# Fathom-S.net
KiCad netlist of a schematic drawn in EAGLE
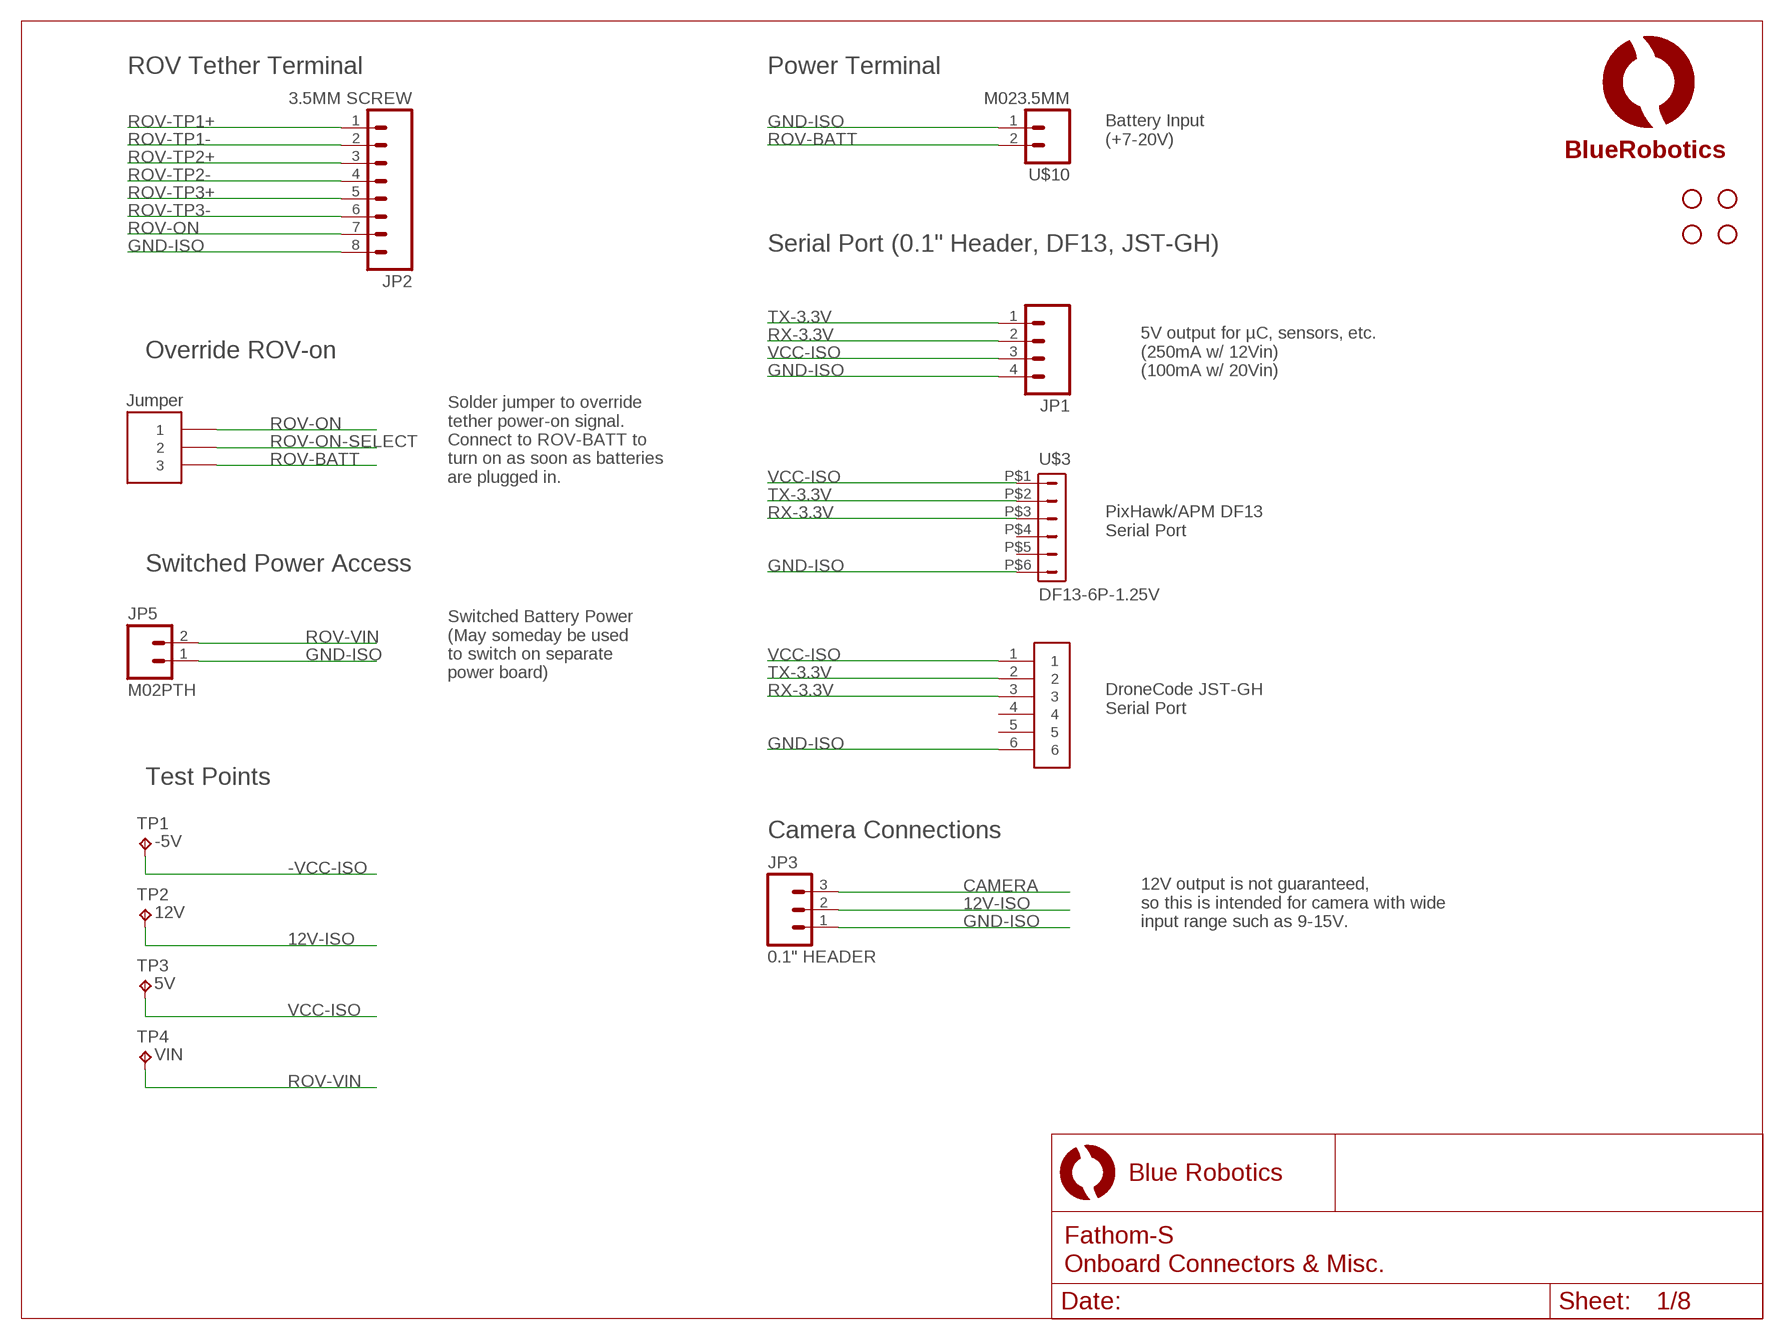
[diagram p0: schematic, sheet 1]
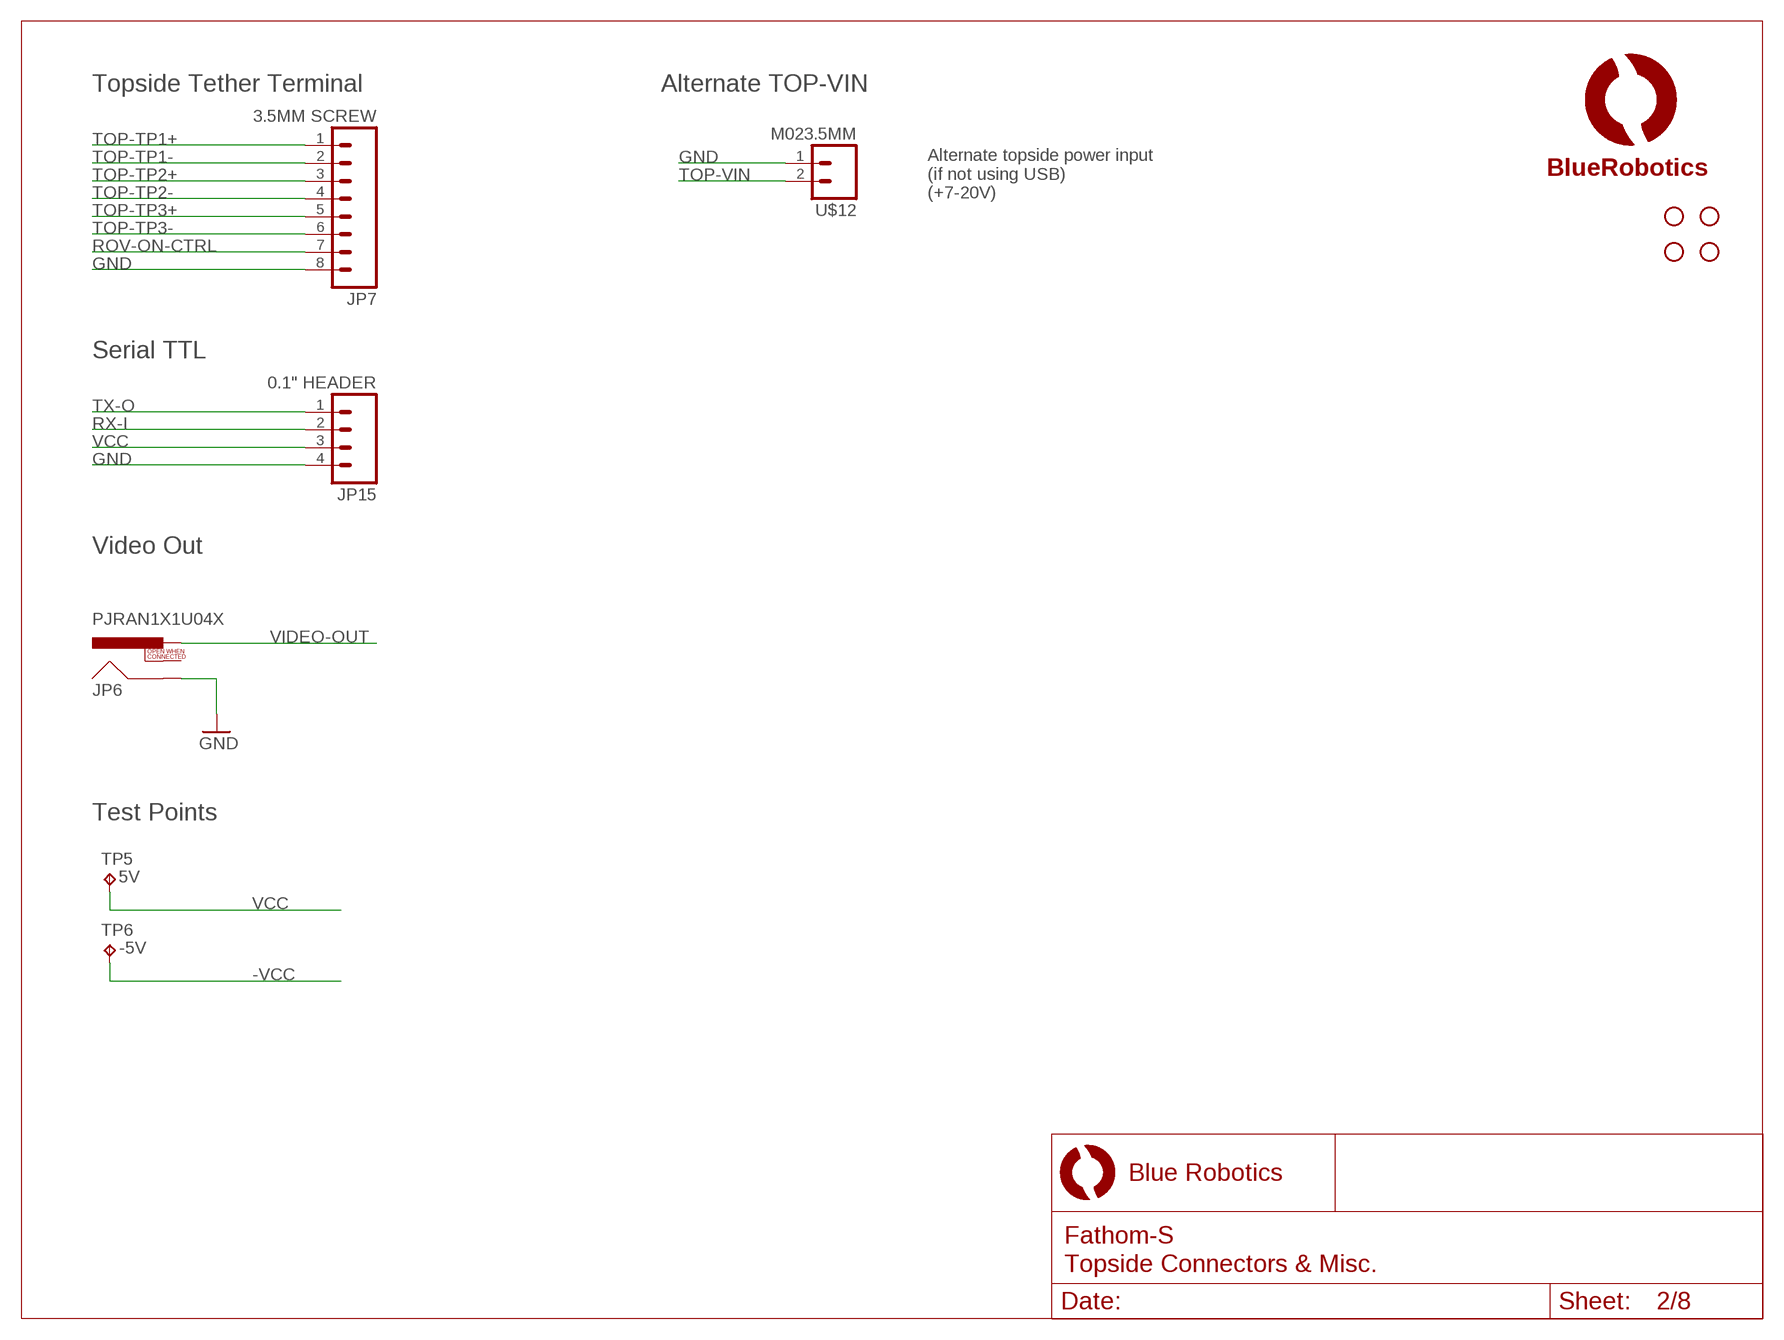
[diagram p1: schematic, sheet 2]
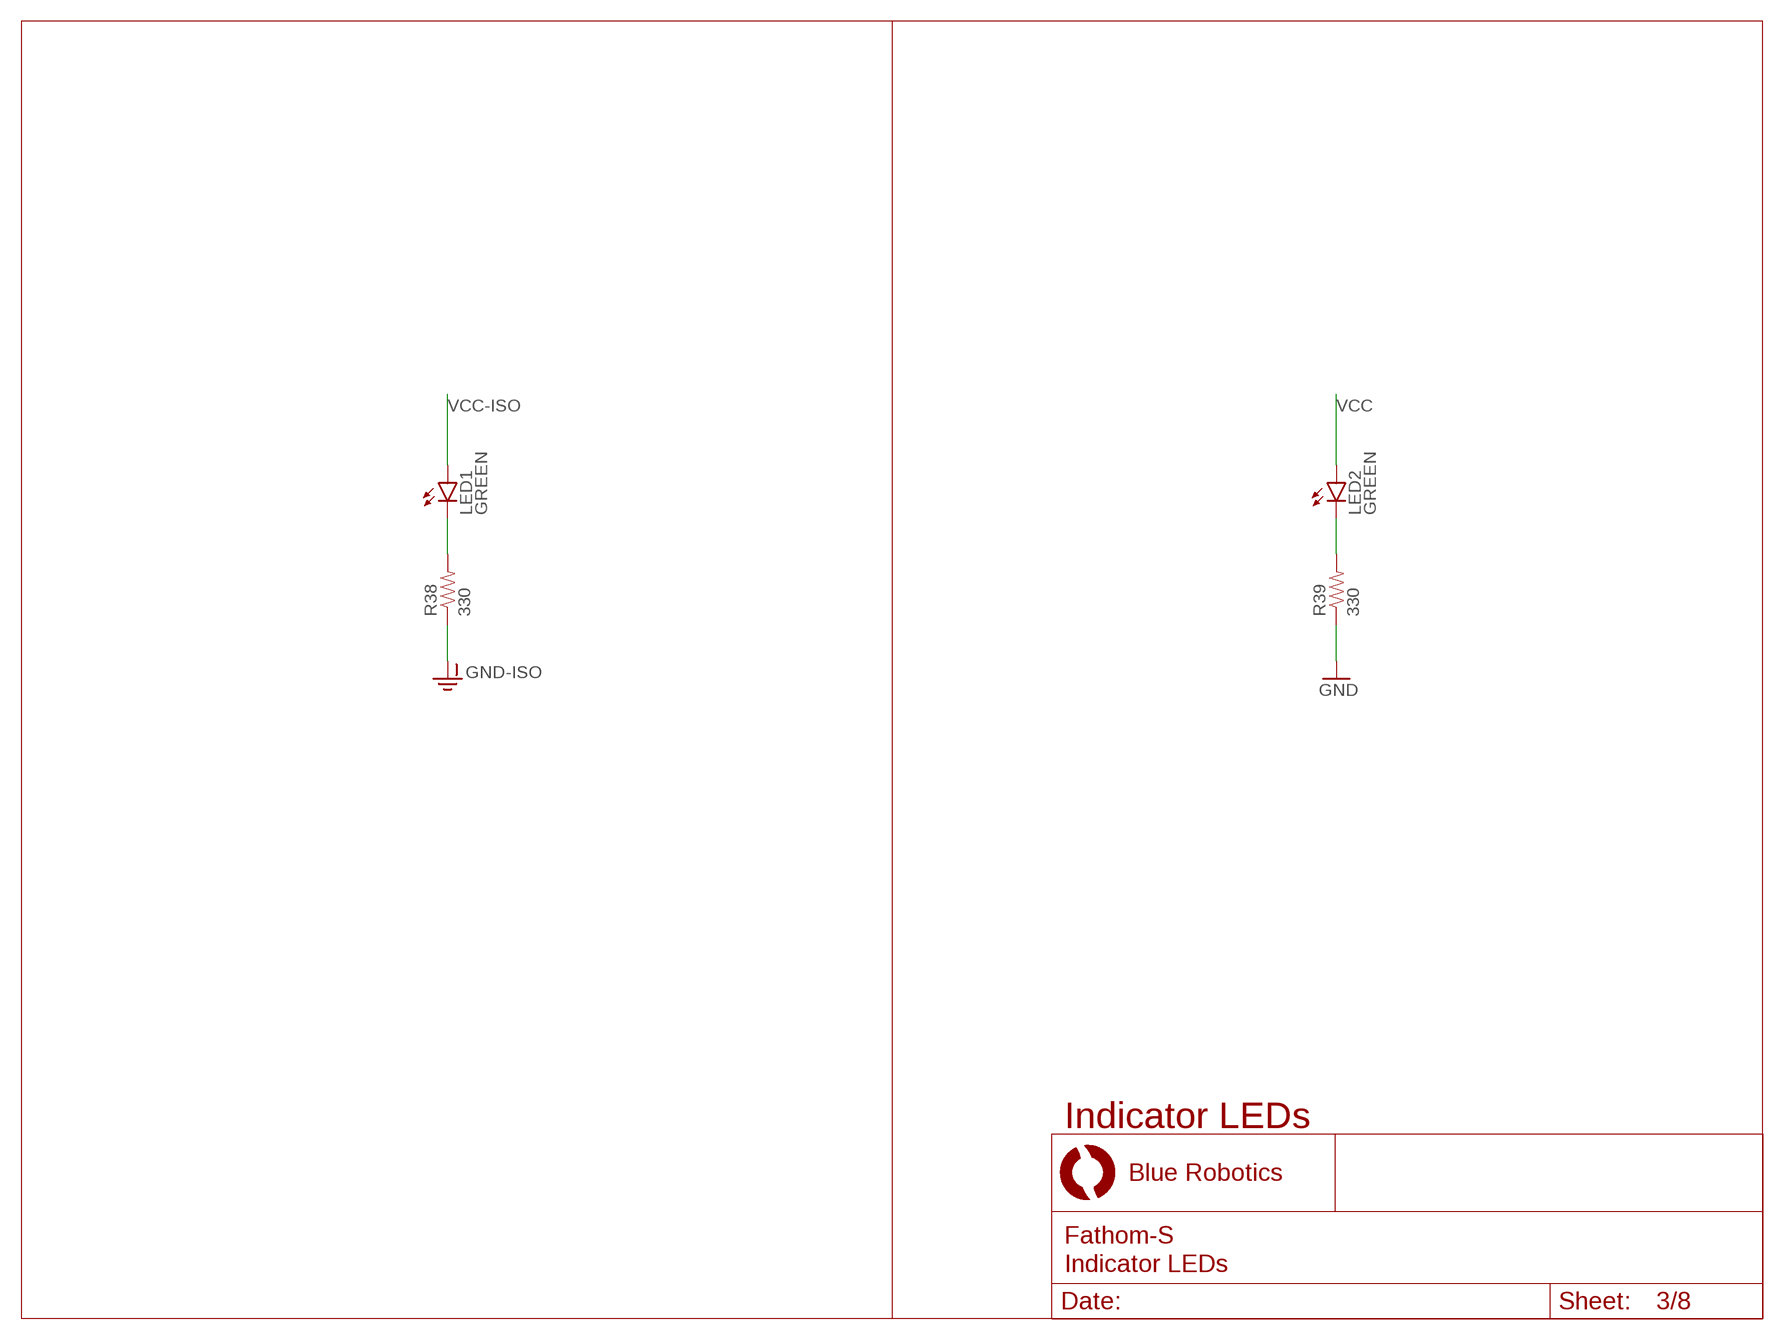
[diagram p2: schematic, sheet 3]
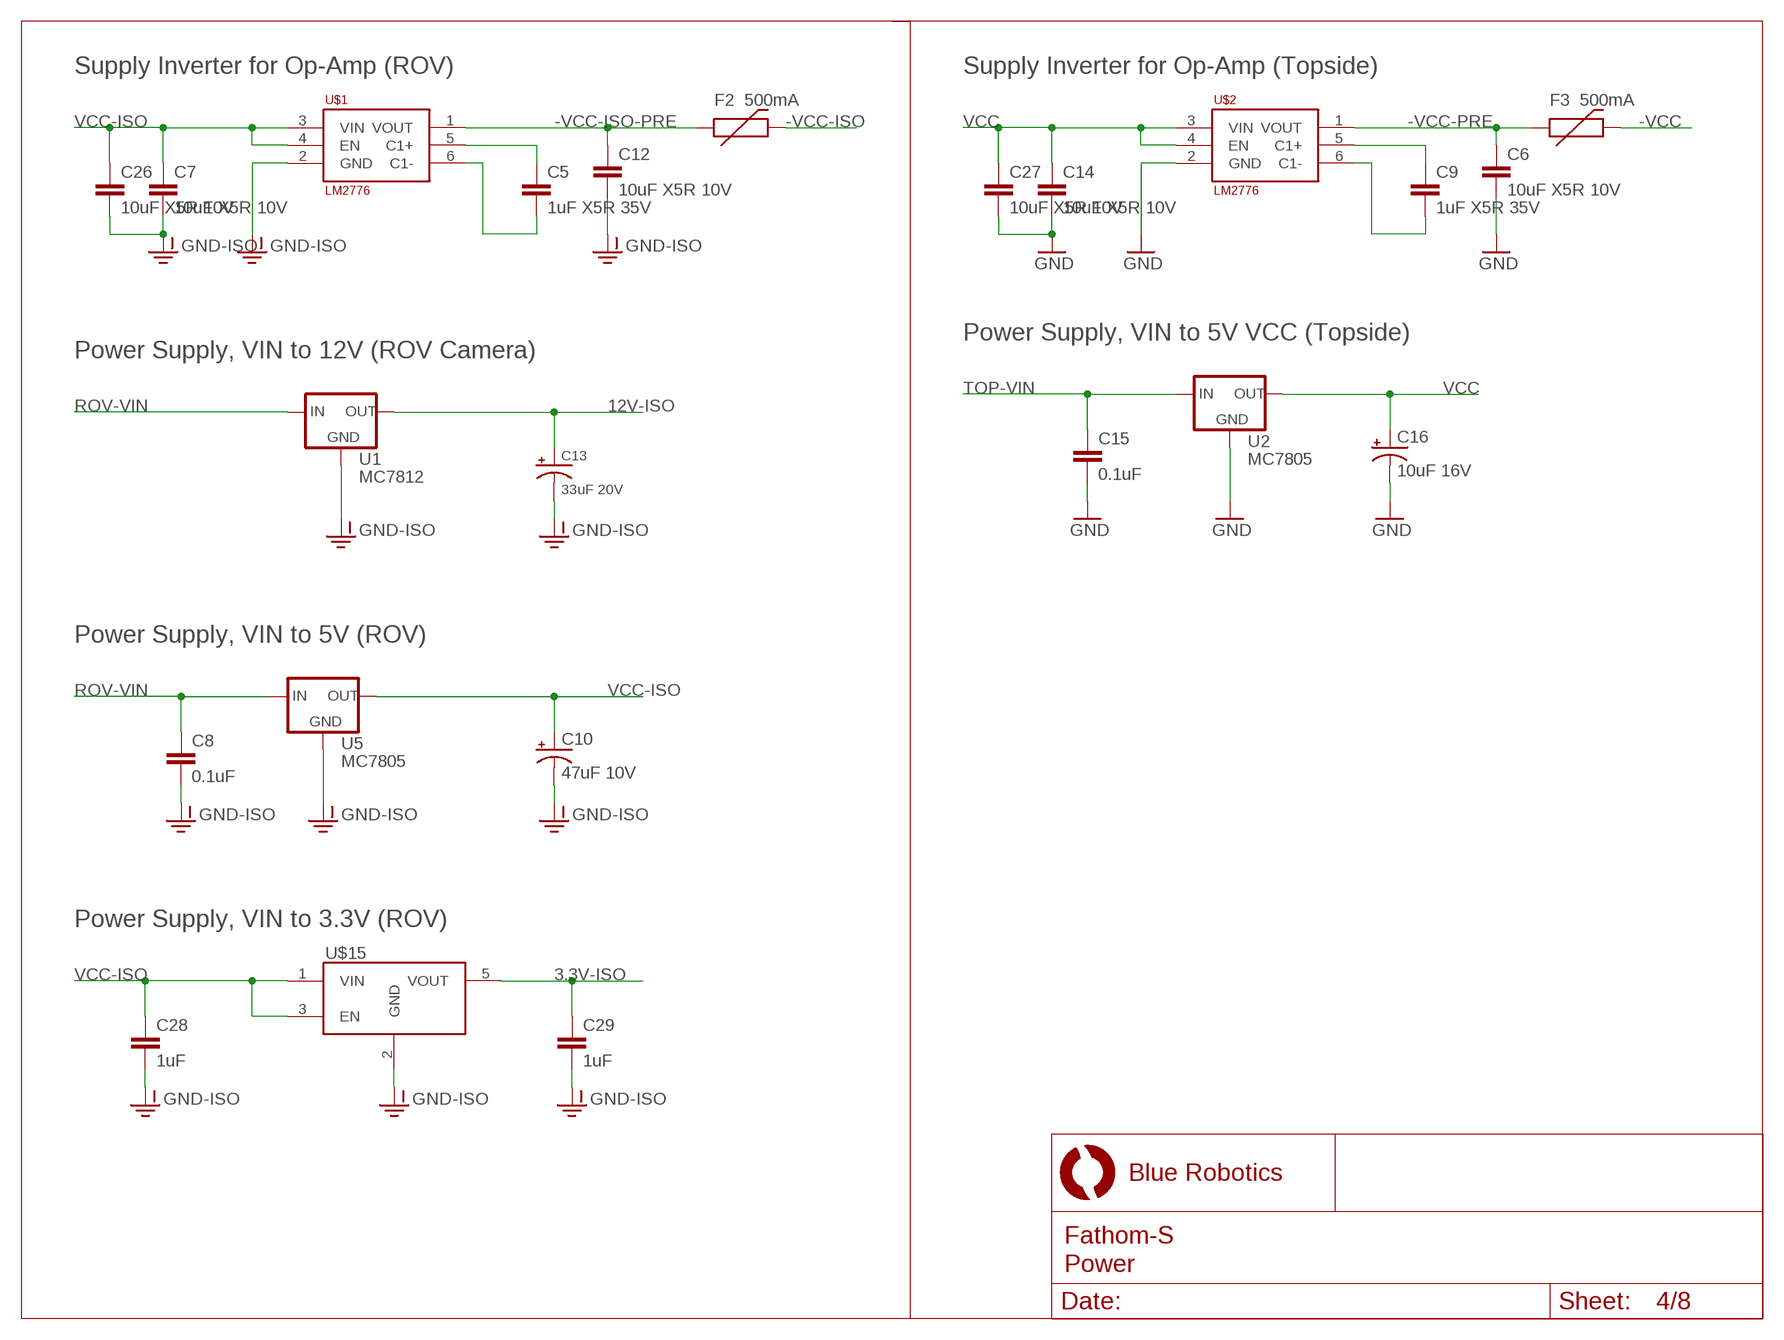
[diagram p3: schematic, sheet 4]
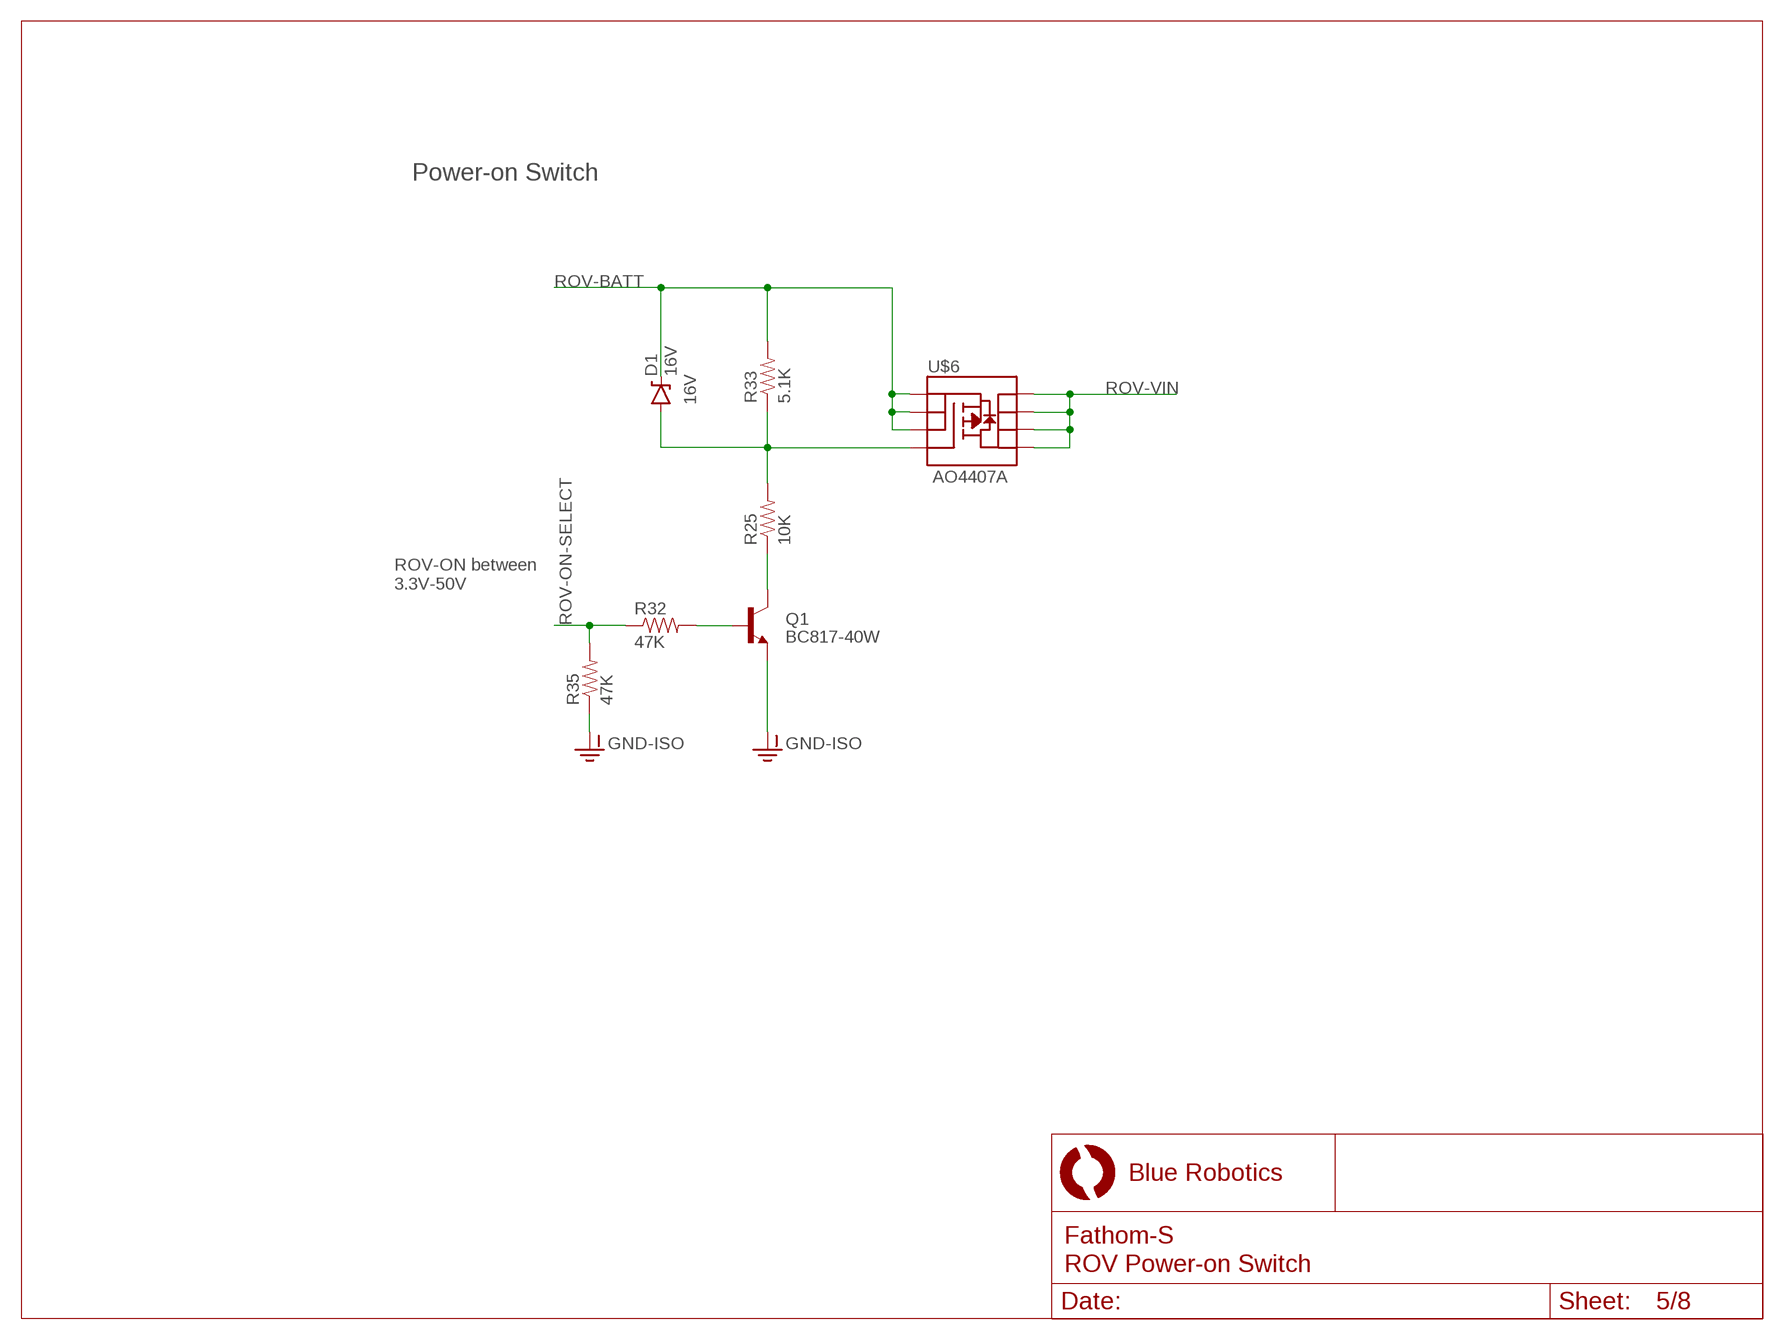
[diagram p4: schematic, sheet 5]
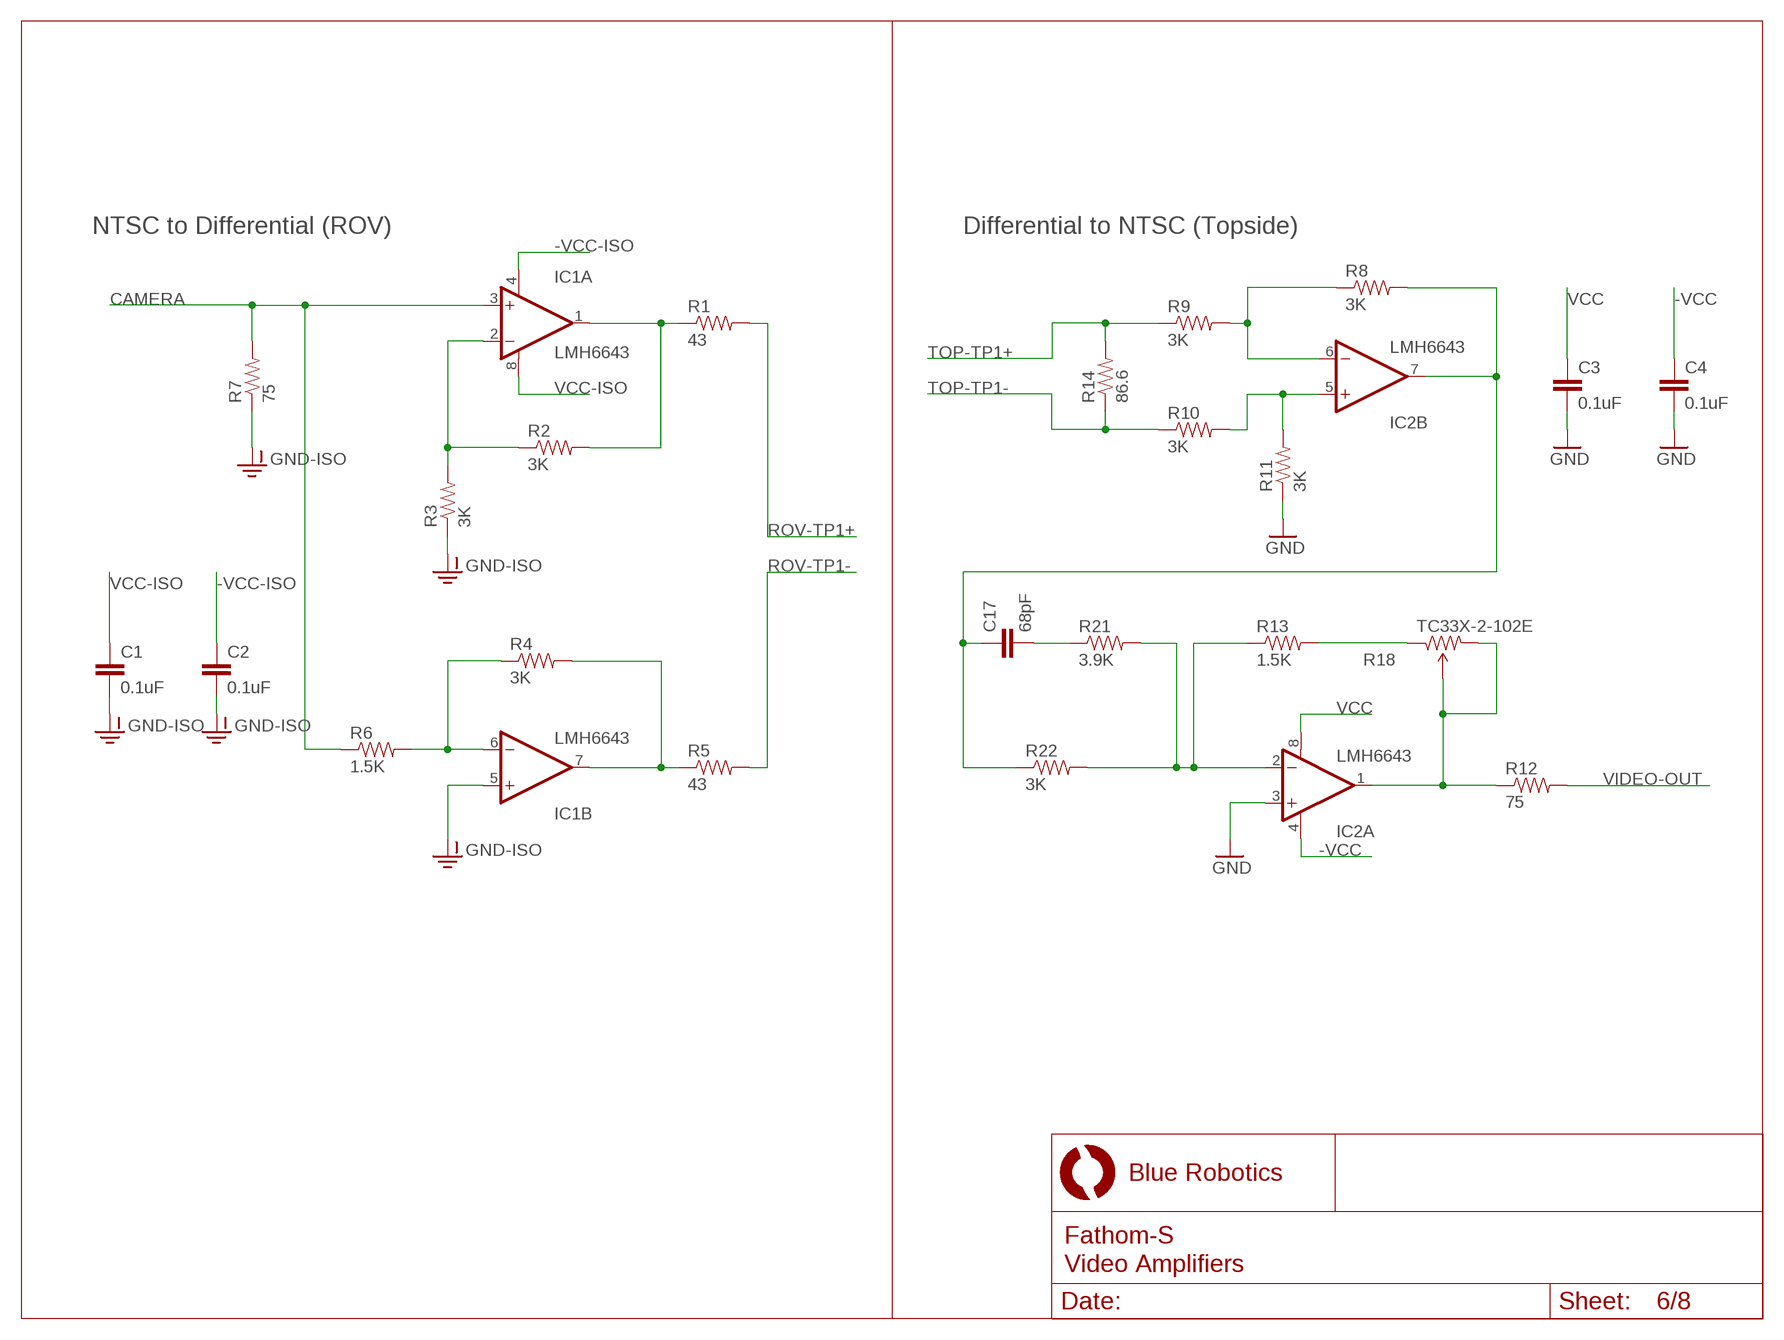
[diagram p5: schematic, sheet 6]
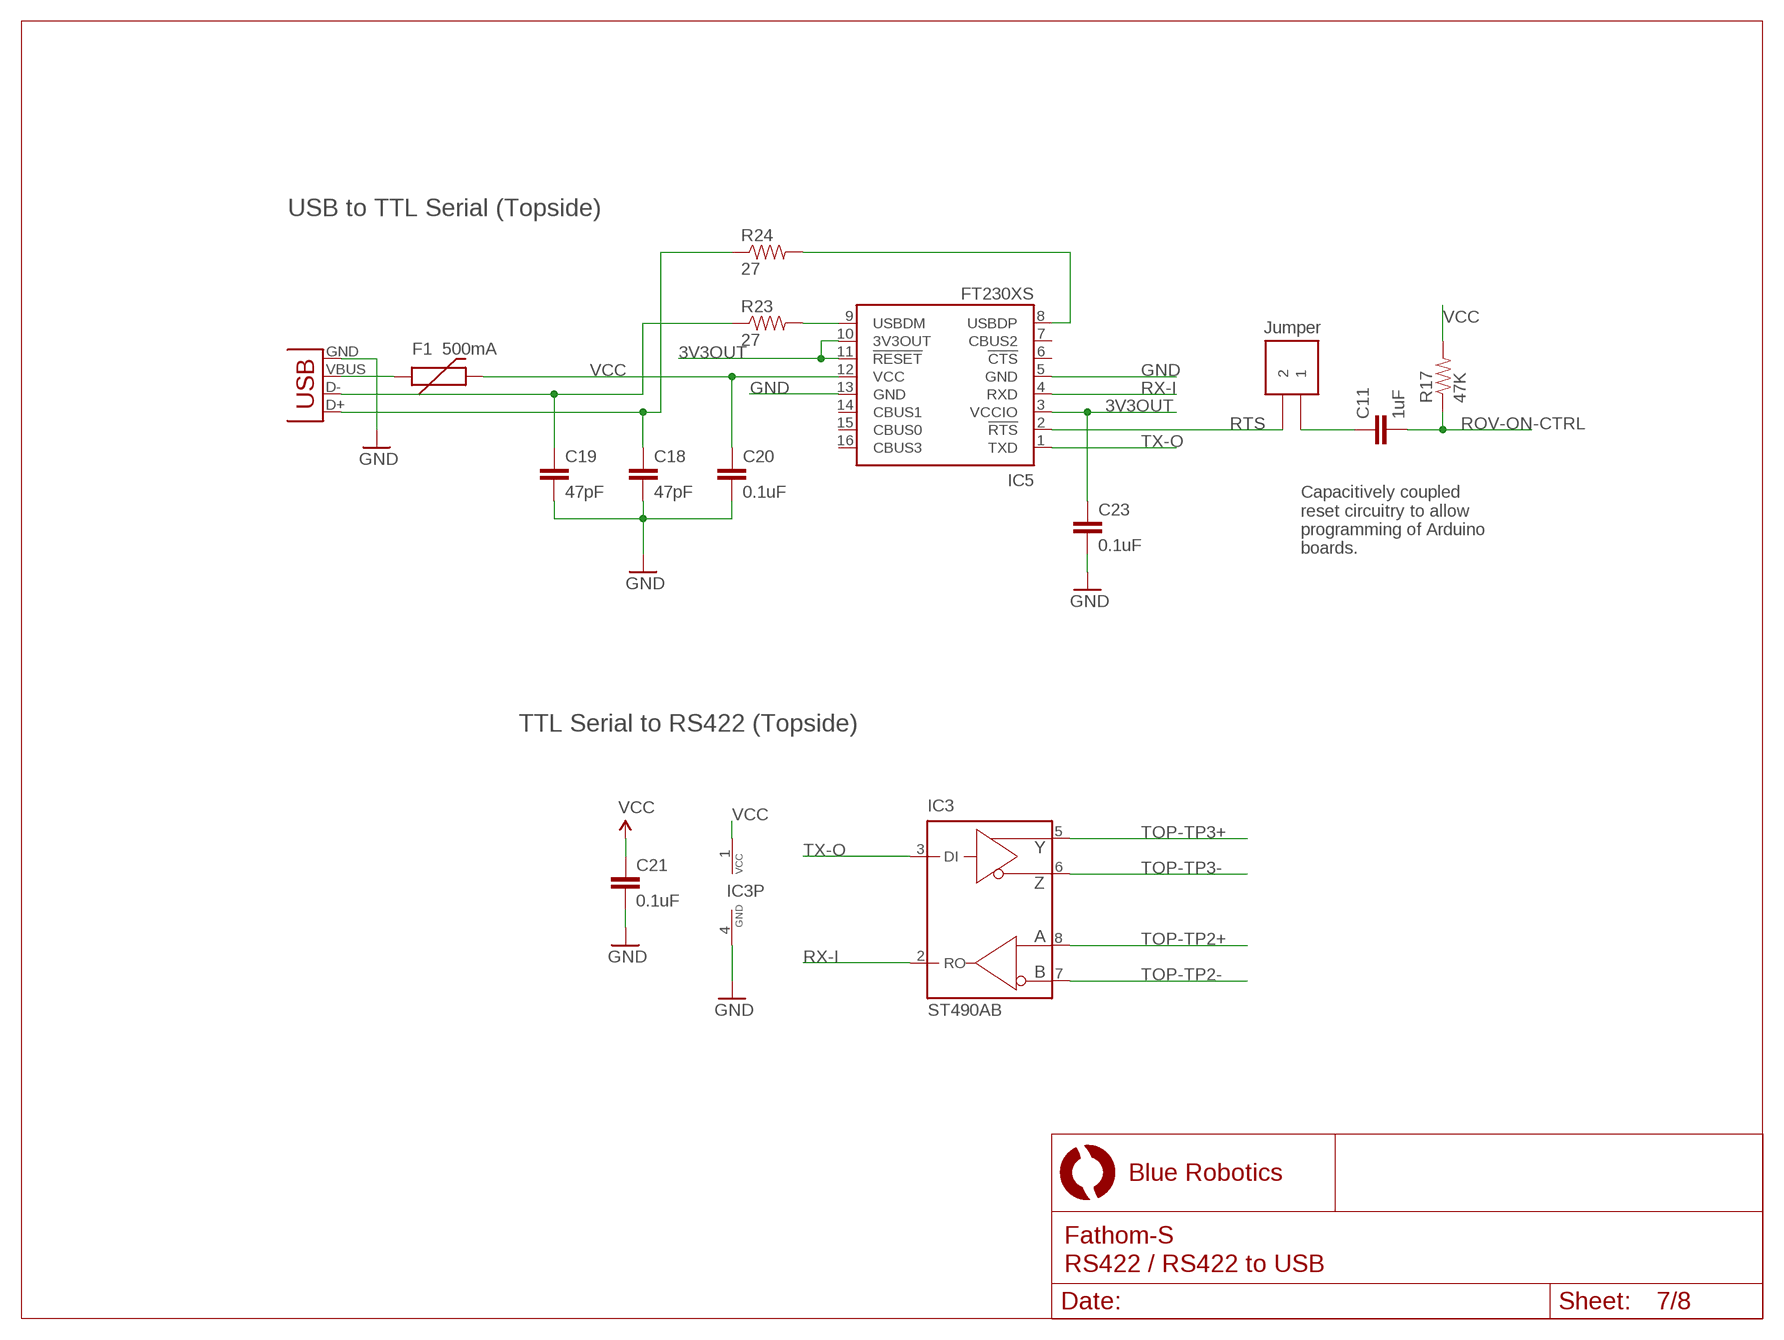
[diagram p6: schematic, sheet 7]
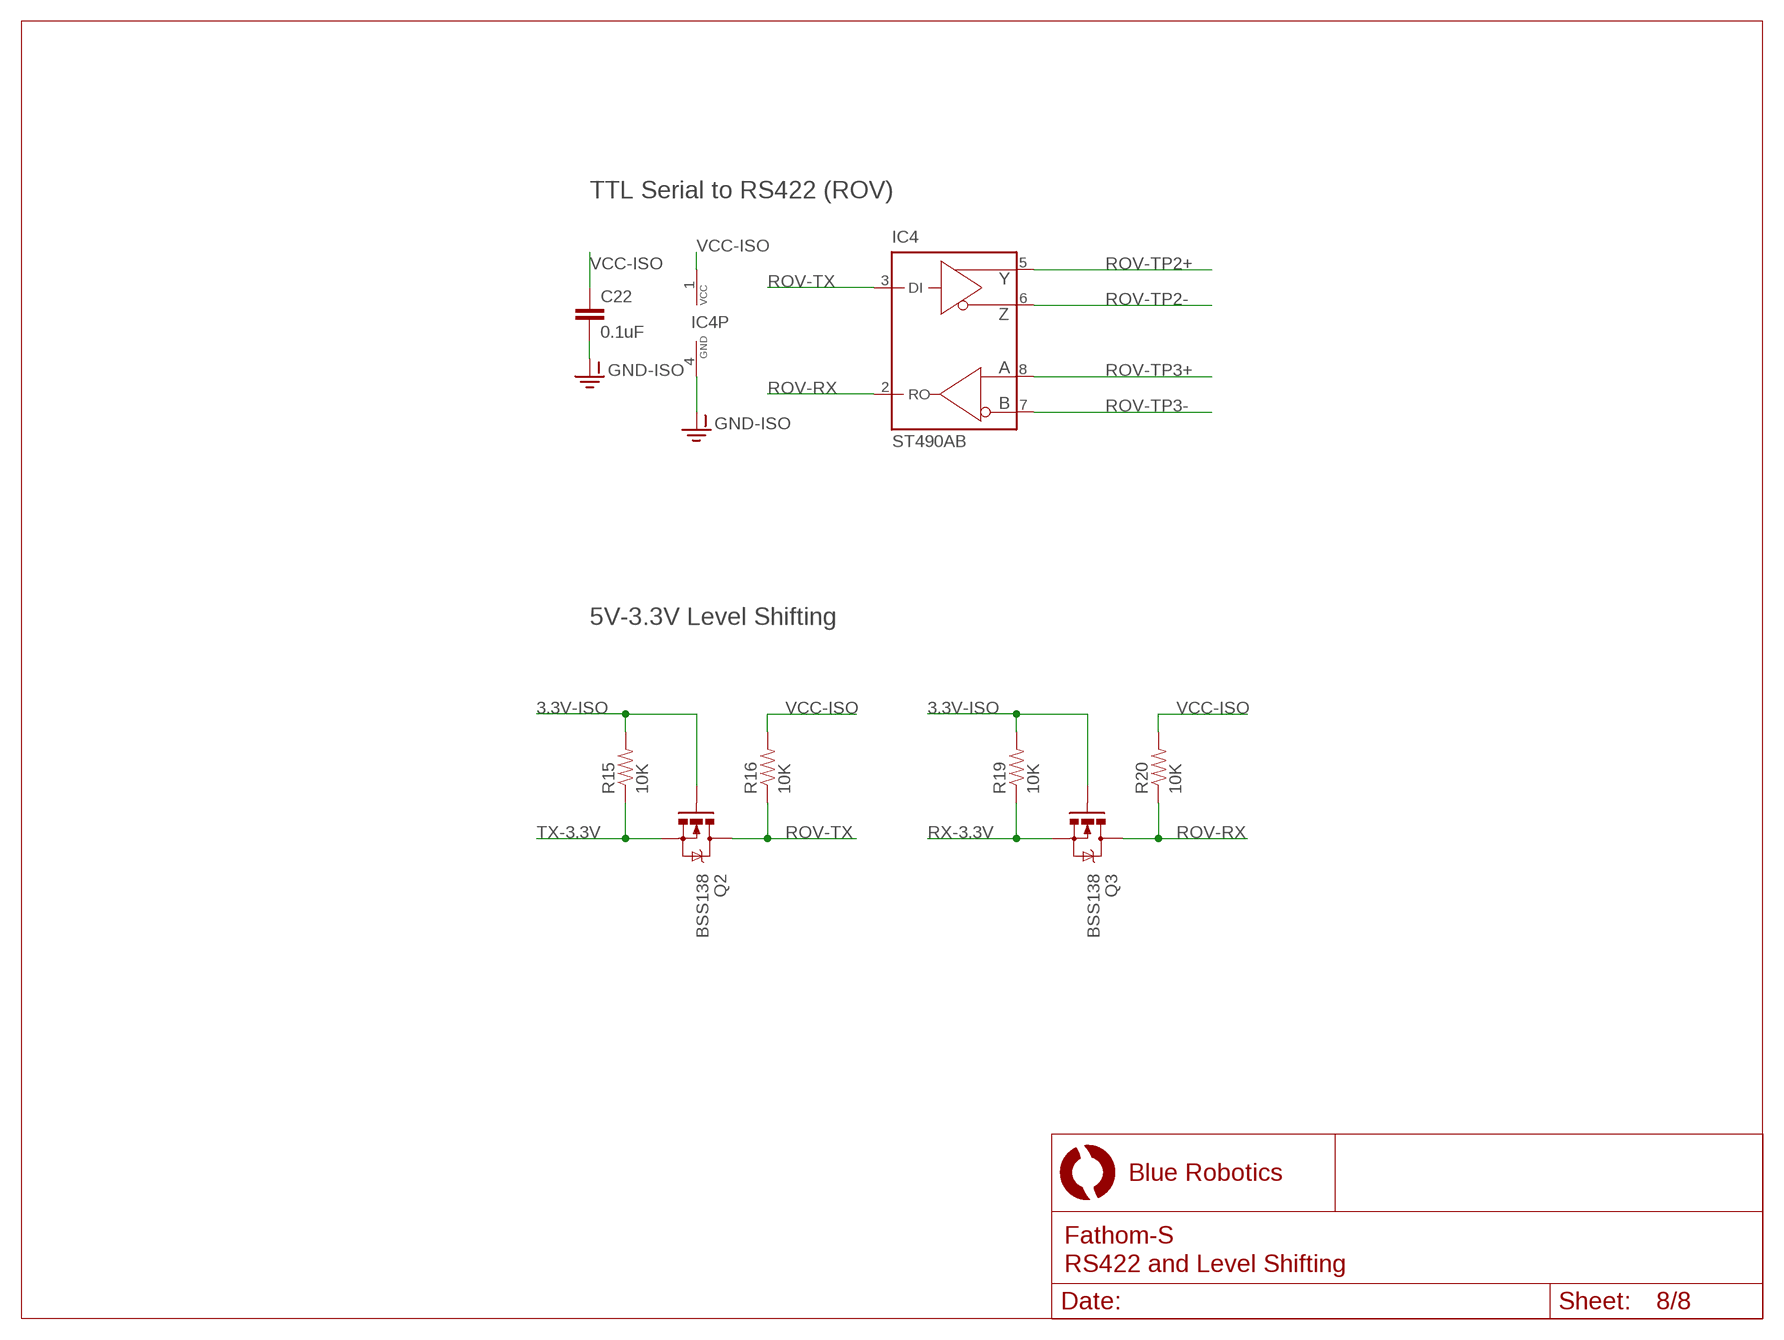
[diagram p7: schematic, sheet 8]

(export (version "E")
  (design (tool "Eeschema 10.0.6"))
  (components
    (comp (ref "LED1")
      (value "GREEN")
      (footprint "eagle-import:LED-0603")
      (libsource (lib "eagle-import") (part "LED0603"))
    )
    (comp (ref "LED2")
      (value "GREEN")
      (footprint "eagle-import:LED-0603")
      (libsource (lib "eagle-import") (part "LED0603"))
    )
    (comp (ref "R38")
      (value "330")
      (footprint "eagle-import:0603-RES")
      (libsource (lib "eagle-import") (part "33KOHM1/10W1%(0603)"))
    )
    (comp (ref "R39")
      (value "330")
      (footprint "eagle-import:0603-RES")
      (libsource (lib "eagle-import") (part "33KOHM1/10W1%(0603)"))
    )
    (comp (ref "C1")
      (value "0.1uF")
      (footprint "eagle-import:0603-CAP")
      (libsource (lib "eagle-import") (part "SparkFun-Passives_CAP0603-CAP"))
    )
    (comp (ref "C2")
      (value "0.1uF")
      (footprint "eagle-import:0603-CAP")
      (libsource (lib "eagle-import") (part "SparkFun-Passives_CAP0603-CAP"))
    )
    (comp (ref "C3")
      (value "0.1uF")
      (footprint "eagle-import:0603-CAP")
      (libsource (lib "eagle-import") (part "SparkFun-Passives_CAP0603-CAP"))
    )
    (comp (ref "C4")
      (value "0.1uF")
      (footprint "eagle-import:0603-CAP")
      (libsource (lib "eagle-import") (part "SparkFun-Passives_CAP0603-CAP"))
    )
    (comp (ref "C17")
      (value "68pF")
      (footprint "eagle-import:0603-CAP")
      (libsource (lib "eagle-import") (part "SparkFun-Passives_CAP0603-CAP"))
    )
    (comp (ref "IC1")
      (value "LMH6643")
      (footprint "eagle-import:MSOP8")
      (libsource (lib "eagle-import") (part "OPAMP-DUALMSOP"))
    )
    (comp (ref "IC2")
      (value "LMH6643")
      (footprint "eagle-import:MSOP8")
      (libsource (lib "eagle-import") (part "OPAMP-DUALMSOP"))
    )
    (comp (ref "R1")
      (value "43")
      (footprint "eagle-import:0603-RES")
      (libsource (lib "eagle-import") (part "SparkFun-Passives_RESISTOR0603-RES"))
    )
    (comp (ref "R2")
      (value "3K")
      (footprint "eagle-import:0603-RES")
      (libsource (lib "eagle-import") (part "SparkFun-Passives_RESISTOR0603-RES"))
    )
    (comp (ref "R3")
      (value "3K")
      (footprint "eagle-import:0603-RES")
      (libsource (lib "eagle-import") (part "SparkFun-Passives_RESISTOR0603-RES"))
    )
    (comp (ref "R4")
      (value "3K")
      (footprint "eagle-import:0603-RES")
      (libsource (lib "eagle-import") (part "SparkFun-Passives_RESISTOR0603-RES"))
    )
    (comp (ref "R5")
      (value "43")
      (footprint "eagle-import:0603-RES")
      (libsource (lib "eagle-import") (part "SparkFun-Passives_RESISTOR0603-RES"))
    )
    (comp (ref "R6")
      (value "1.5K")
      (footprint "eagle-import:0603-RES")
      (libsource (lib "eagle-import") (part "SparkFun-Passives_RESISTOR0603-RES"))
    )
    (comp (ref "R7")
      (value "75")
      (footprint "eagle-import:0603-RES")
      (libsource (lib "eagle-import") (part "SparkFun-Passives_RESISTOR0603-RES"))
    )
    (comp (ref "R8")
      (value "3K")
      (footprint "eagle-import:0603-RES")
      (libsource (lib "eagle-import") (part "SparkFun-Passives_RESISTOR0603-RES"))
    )
    (comp (ref "R9")
      (value "3K")
      (footprint "eagle-import:0603-RES")
      (libsource (lib "eagle-import") (part "SparkFun-Passives_RESISTOR0603-RES"))
    )
    (comp (ref "R10")
      (value "3K")
      (footprint "eagle-import:0603-RES")
      (libsource (lib "eagle-import") (part "SparkFun-Passives_RESISTOR0603-RES"))
    )
    (comp (ref "R11")
      (value "3K")
      (footprint "eagle-import:0603-RES")
      (libsource (lib "eagle-import") (part "SparkFun-Passives_RESISTOR0603-RES"))
    )
    (comp (ref "R12")
      (value "75")
      (footprint "eagle-import:0603-RES")
      (libsource (lib "eagle-import") (part "SparkFun-Passives_RESISTOR0603-RES"))
    )
    (comp (ref "R13")
      (value "1.5K")
      (footprint "eagle-import:0603-RES")
      (libsource (lib "eagle-import") (part "SparkFun-Passives_RESISTOR0603-RES"))
    )
    (comp (ref "R14")
      (value "86.6")
      (footprint "eagle-import:0603-RES")
      (libsource (lib "eagle-import") (part "SparkFun-Passives_RESISTOR0603-RES"))
    )
    (comp (ref "R18")
      (value "TC33X-2-102E")
      (footprint "eagle-import:TRIMPOT_TC33")
      (libsource (lib "eagle-import") (part "TRIMPOT-2"))
    )
    (comp (ref "R21")
      (value "3.9K")
      (footprint "eagle-import:0603-RES")
      (libsource (lib "eagle-import") (part "SparkFun-Passives_RESISTOR0603-RES"))
    )
    (comp (ref "R22")
      (value "3K")
      (footprint "eagle-import:0603-RES")
      (libsource (lib "eagle-import") (part "SparkFun-Passives_RESISTOR0603-RES"))
    )
    (comp (ref "JP6")
      (value "PJRAN1X1U04X")
      (footprint "eagle-import:RCA")
      (libsource (lib "eagle-import") (part "RCA"))
    )
    (comp (ref "JP7")
      (value "3.5MM SCREW")
      (footprint "eagle-import:SCREWTERMINAL-3.5MM-8")
      (libsource (lib "eagle-import") (part "M083.5MM-8"))
    )
    (comp (ref "JP15")
      (value "0.1\" HEADER")
      (footprint "eagle-import:1X04")
      (libsource (lib "eagle-import") (part "M04PTH"))
    )
    (comp (ref "STANDOFF5")
      (value "STAND-OFF")
      (footprint "eagle-import:STAND-OFF")
      (libsource (lib "eagle-import") (part "STAND-OFF"))
    )
    (comp (ref "STANDOFF6")
      (value "STAND-OFF")
      (footprint "eagle-import:STAND-OFF")
      (libsource (lib "eagle-import") (part "STAND-OFF"))
    )
    (comp (ref "STANDOFF7")
      (value "STAND-OFF")
      (footprint "eagle-import:STAND-OFF")
      (libsource (lib "eagle-import") (part "STAND-OFF"))
    )
    (comp (ref "STANDOFF8")
      (value "STAND-OFF")
      (footprint "eagle-import:STAND-OFF")
      (libsource (lib "eagle-import") (part "STAND-OFF"))
    )
    (comp (ref "TP5")
      (value "5V")
      (footprint "eagle-import:B1,27")
      (libsource (lib "eagle-import") (part "TEST-POINT"))
    )
    (comp (ref "TP6")
      (value "-5V")
      (footprint "eagle-import:B1,27")
      (libsource (lib "eagle-import") (part "TEST-POINT"))
    )
    (comp (ref "U$5")
      (value "LOGOBR-LOGO-MS-COPPER")
      (footprint "eagle-import:BR-LOGO-MEDIUM-SMALL-COPPER")
      (libsource (lib "eagle-import") (part "LOGOBR-LOGO-MS-COPPER"))
    )
    (comp (ref "U$12")
      (value "M023.5MM")
      (footprint "eagle-import:SCREWTERMINAL-3.5MM-2")
      (libsource (lib "eagle-import") (part "M023.5MM"))
    )
    (comp (ref "C22")
      (value "0.1uF")
      (footprint "eagle-import:0603-CAP")
      (libsource (lib "eagle-import") (part "CAP0603-CAP"))
    )
    (comp (ref "IC4")
      (value "ST490AB")
      (footprint "eagle-import:SO08")
      (fields (field (name "MF") "MAXIM") (field (name "MPN") "MAX488CSA"))
      (libsource (lib "eagle-import") (part "MAX488CSA"))
    )
    (comp (ref "Q2")
      (value "BSS138")
      (footprint "eagle-import:SOT23")
      (libsource (lib "eagle-import") (part "MOSFET-NCHANNELBSS138"))
    )
    (comp (ref "Q3")
      (value "BSS138")
      (footprint "eagle-import:SOT23")
      (libsource (lib "eagle-import") (part "MOSFET-NCHANNELBSS138"))
    )
    (comp (ref "R15")
      (value "10K")
      (footprint "eagle-import:0603-RES")
      (libsource (lib "eagle-import") (part "RESISTOR0603-RES"))
    )
    (comp (ref "R16")
      (value "10K")
      (footprint "eagle-import:0603-RES")
      (libsource (lib "eagle-import") (part "RESISTOR0603-RES"))
    )
    (comp (ref "R19")
      (value "10K")
      (footprint "eagle-import:0603-RES")
      (libsource (lib "eagle-import") (part "RESISTOR0603-RES"))
    )
    (comp (ref "R20")
      (value "10K")
      (footprint "eagle-import:0603-RES")
      (libsource (lib "eagle-import") (part "RESISTOR0603-RES"))
    )
    (comp (ref "JP1")
      (value "M04PTH")
      (footprint "eagle-import:1X04")
      (libsource (lib "eagle-import") (part "M04PTH"))
    )
    (comp (ref "JP2")
      (value "3.5MM SCREW")
      (footprint "eagle-import:SCREWTERMINAL-3.5MM-8")
      (libsource (lib "eagle-import") (part "M083.5MM-8"))
    )
    (comp (ref "JP3")
      (value "0.1\" HEADER")
      (footprint "eagle-import:1X03")
      (libsource (lib "eagle-import") (part "M03PTH"))
    )
    (comp (ref "JP5")
      (value "M02PTH")
      (footprint "eagle-import:1X02")
      (libsource (lib "eagle-import") (part "M02PTH"))
    )
    (comp (ref "STANDOFF1")
      (value "STAND-OFF")
      (footprint "eagle-import:STAND-OFF")
      (libsource (lib "eagle-import") (part "STAND-OFF"))
    )
    (comp (ref "STANDOFF2")
      (value "STAND-OFF")
      (footprint "eagle-import:STAND-OFF")
      (libsource (lib "eagle-import") (part "STAND-OFF"))
    )
    (comp (ref "STANDOFF3")
      (value "STAND-OFF")
      (footprint "eagle-import:STAND-OFF")
      (libsource (lib "eagle-import") (part "STAND-OFF"))
    )
    (comp (ref "STANDOFF4")
      (value "STAND-OFF")
      (footprint "eagle-import:STAND-OFF")
      (libsource (lib "eagle-import") (part "STAND-OFF"))
    )
    (comp (ref "TP1")
      (value "-5V")
      (footprint "eagle-import:B1,27")
      (libsource (lib "eagle-import") (part "TEST-POINT"))
    )
    (comp (ref "TP2")
      (value "12V")
      (footprint "eagle-import:B1,27")
      (libsource (lib "eagle-import") (part "TEST-POINT"))
    )
    (comp (ref "TP3")
      (value "5V")
      (footprint "eagle-import:B1,27")
      (libsource (lib "eagle-import") (part "TEST-POINT"))
    )
    (comp (ref "TP4")
      (value "VIN")
      (footprint "eagle-import:B1,27")
      (libsource (lib "eagle-import") (part "TEST-POINT"))
    )
    (comp (ref "U$3")
      (value "DF13-6P-1.25V")
      (footprint "eagle-import:DF13C-6P-1.25V")
      (libsource (lib "eagle-import") (part "DF13-6P-1.25V"))
    )
    (comp (ref "U$4")
      (value "LOGOFULL-M")
      (footprint "eagle-import:BR-FULL-LOGO-MEDIUM")
      (libsource (lib "eagle-import") (part "LOGOFULL-M"))
    )
    (comp (ref "U$10")
      (value "M023.5MM")
      (footprint "eagle-import:SCREWTERMINAL-3.5MM-2")
      (libsource (lib "eagle-import") (part "M023.5MM"))
    )
    (comp (ref "U$11")
      (value "JST-GH-6TOP-ENTRY")
      (footprint "eagle-import:JST-GH-TOP-6")
      (libsource (lib "eagle-import") (part "JST-GH-6TOP-ENTRY"))
    )
    (comp (ref "U$13")
      (value "HEADER-33MM")
      (footprint "eagle-import:HEADER-2MM-3POS")
      (libsource (lib "eagle-import") (part "HEADER-33MM"))
    )
    (comp (ref "C11")
      (value "1uF")
      (footprint "eagle-import:0603-CAP")
      (libsource (lib "eagle-import") (part "CAP0603-CAP"))
    )
    (comp (ref "C18")
      (value "47pF")
      (footprint "eagle-import:0603-CAP")
      (libsource (lib "eagle-import") (part "CAP0603-CAP"))
    )
    (comp (ref "C19")
      (value "47pF")
      (footprint "eagle-import:0603-CAP")
      (libsource (lib "eagle-import") (part "CAP0603-CAP"))
    )
    (comp (ref "C20")
      (value "0.1uF")
      (footprint "eagle-import:0603-CAP")
      (libsource (lib "eagle-import") (part "CAP0603-CAP"))
    )
    (comp (ref "C21")
      (value "0.1uF")
      (footprint "eagle-import:0603-CAP")
      (libsource (lib "eagle-import") (part "CAP0603-CAP"))
    )
    (comp (ref "C23")
      (value "0.1uF")
      (footprint "eagle-import:0603-CAP")
      (libsource (lib "eagle-import") (part "CAP0603-CAP"))
    )
    (comp (ref "F1")
      (value "500mA")
      (footprint "eagle-import:0603")
      (libsource (lib "eagle-import") (part "PTC0603"))
    )
    (comp (ref "IC3")
      (value "ST490AB")
      (footprint "eagle-import:SO08")
      (fields (field (name "MF") "MAXIM") (field (name "MPN") "MAX488CSA"))
      (libsource (lib "eagle-import") (part "MAX488CSA"))
    )
    (comp (ref "IC5")
      (value "FT230XS")
      (footprint "eagle-import:SSOP16")
      (libsource (lib "eagle-import") (part "FT230XS"))
    )
    (comp (ref "R17")
      (value "47K")
      (footprint "eagle-import:0603-RES")
      (libsource (lib "eagle-import") (part "RESISTOR0603-RES"))
    )
    (comp (ref "R23")
      (value "27")
      (footprint "eagle-import:0603-RES")
      (libsource (lib "eagle-import") (part "RESISTOR0603-RES"))
    )
    (comp (ref "R24")
      (value "27")
      (footprint "eagle-import:0603-RES")
      (libsource (lib "eagle-import") (part "RESISTOR0603-RES"))
    )
    (comp (ref "U$16")
      (value "HEADER-22MM")
      (footprint "eagle-import:HEADER-2MM-2POS")
      (libsource (lib "eagle-import") (part "HEADER-22MM"))
    )
    (comp (ref "X2")
      (value "USBSMD")
      (footprint "eagle-import:USB-MINIB")
      (libsource (lib "eagle-import") (part "USBSMD"))
    )
    (comp (ref "D1")
      (value "16V")
      (footprint "eagle-import:SOD-323")
      (libsource (lib "eagle-import") (part "DIODE-ZENER3.3V"))
    )
    (comp (ref "Q1")
      (value "BC817-40W")
      (footprint "eagle-import:SOT23")
      (libsource (lib "eagle-import") (part "TRANSISTOR_NPNSOT23"))
    )
    (comp (ref "R25")
      (value "10K")
      (footprint "eagle-import:0603-RES")
      (libsource (lib "eagle-import") (part "33KOHM1/10W1%(0603)"))
    )
    (comp (ref "R32")
      (value "47K")
      (footprint "eagle-import:0603-RES")
      (libsource (lib "eagle-import") (part "33KOHM1/10W1%(0603)"))
    )
    (comp (ref "R33")
      (value "5.1K")
      (footprint "eagle-import:0603-RES")
      (libsource (lib "eagle-import") (part "33KOHM1/10W1%(0603)"))
    )
    (comp (ref "R35")
      (value "47K")
      (footprint "eagle-import:0603-RES")
      (libsource (lib "eagle-import") (part "33KOHM1/10W1%(0603)"))
    )
    (comp (ref "U$6")
      (value "AO4407A")
      (footprint "eagle-import:SO08")
      (libsource (lib "eagle-import") (part "MOSFET-PCHANNEL-SOIC8SOIC8"))
    )
    (comp (ref "C5")
      (value "1uF X5R 35V")
      (footprint "eagle-import:0603-CAP")
      (libsource (lib "eagle-import") (part "SparkFun-Passives_CAP0603-CAP"))
    )
    (comp (ref "C6")
      (value "10uF X5R 10V")
      (footprint "eagle-import:0805")
      (libsource (lib "eagle-import") (part "SparkFun-Passives_CAP0805"))
    )
    (comp (ref "C7")
      (value "10uF X5R 10V")
      (footprint "eagle-import:0805")
      (libsource (lib "eagle-import") (part "SparkFun-Passives_CAP0805"))
    )
    (comp (ref "C8")
      (value "0.1uF")
      (footprint "eagle-import:0603-CAP")
      (libsource (lib "eagle-import") (part "SparkFun-Passives_CAP0603-CAP"))
    )
    (comp (ref "C9")
      (value "1uF X5R 35V")
      (footprint "eagle-import:0603-CAP")
      (libsource (lib "eagle-import") (part "SparkFun-Passives_CAP0603-CAP"))
    )
    (comp (ref "C10")
      (value "47uF 10V")
      (footprint "eagle-import:EIA3528")
      (libsource (lib "eagle-import") (part "CAP_POL3528"))
    )
    (comp (ref "C12")
      (value "10uF X5R 10V")
      (footprint "eagle-import:0805")
      (libsource (lib "eagle-import") (part "SparkFun-Passives_CAP0805"))
    )
    (comp (ref "C13")
      (value "33uF 20V")
      (footprint "eagle-import:C2413")
      (libsource (lib "eagle-import") (part "CAPACITOR-POLAR2413"))
    )
    (comp (ref "C14")
      (value "10uF X5R 10V")
      (footprint "eagle-import:0805")
      (libsource (lib "eagle-import") (part "SparkFun-Passives_CAP0805"))
    )
    (comp (ref "C15")
      (value "0.1uF")
      (footprint "eagle-import:0603-CAP")
      (libsource (lib "eagle-import") (part "SparkFun-Passives_CAP0603-CAP"))
    )
    (comp (ref "C16")
      (value "10uF 16V")
      (footprint "eagle-import:EIA3216")
      (libsource (lib "eagle-import") (part "CAP_POL1206"))
    )
    (comp (ref "C26")
      (value "10uF X5R 10V")
      (footprint "eagle-import:0805")
      (libsource (lib "eagle-import") (part "SparkFun-Passives_CAP0805"))
    )
    (comp (ref "C27")
      (value "10uF X5R 10V")
      (footprint "eagle-import:0805")
      (libsource (lib "eagle-import") (part "SparkFun-Passives_CAP0805"))
    )
    (comp (ref "C28")
      (value "1uF")
      (footprint "eagle-import:0603-CAP")
      (libsource (lib "eagle-import") (part "SparkFun-Passives_CAP0603-CAP"))
    )
    (comp (ref "C29")
      (value "1uF")
      (footprint "eagle-import:0603-CAP")
      (libsource (lib "eagle-import") (part "SparkFun-Passives_CAP0603-CAP"))
    )
    (comp (ref "F2")
      (value "500mA")
      (footprint "eagle-import:0603")
      (libsource (lib "eagle-import") (part "PTC0603"))
    )
    (comp (ref "F3")
      (value "500mA")
      (footprint "eagle-import:0603")
      (libsource (lib "eagle-import") (part "PTC0603"))
    )
    (comp (ref "U$1")
      (value "LM2776")
      (footprint "eagle-import:SOT-23-6")
      (libsource (lib "eagle-import") (part "LM2776"))
    )
    (comp (ref "U$2")
      (value "LM2776")
      (footprint "eagle-import:SOT-23-6")
      (libsource (lib "eagle-import") (part "LM2776"))
    )
    (comp (ref "U$15")
      (value "VREG-MIC5365")
      (footprint "eagle-import:SC70-5L")
      (libsource (lib "eagle-import") (part "VREG-MIC5365"))
    )
    (comp (ref "U1")
      (value "MC7812")
      (footprint "eagle-import:DPAK")
      (libsource (lib "eagle-import") (part "78XX"))
    )
    (comp (ref "U2")
      (value "MC7805")
      (footprint "eagle-import:DPAK")
      (libsource (lib "eagle-import") (part "78XX"))
    )
    (comp (ref "U5")
      (value "MC7805")
      (footprint "eagle-import:DPAK")
      (libsource (lib "eagle-import") (part "78XX"))
    )
  )
  (nets
    (net (code "1") (name "-VCC") (class "Default")
      (node (ref "C4") (pin "1") (pinfunction "1_1") (pintype "passive"))
      (node (ref "F3") (pin "2") (pinfunction "2_2") (pintype "bidirectional"))
      (node (ref "IC2") (pin "4") (pinfunction "V-_4") (pintype "power_in"))
      (node (ref "TP6") (pin "TP") (pinfunction "TP_TP") (pintype "input"))
    )
    (net (code "2") (name "-VCC-ISO") (class "Default")
      (node (ref "C2") (pin "1") (pinfunction "1_1") (pintype "passive"))
      (node (ref "F2") (pin "2") (pinfunction "2_2") (pintype "bidirectional"))
      (node (ref "IC1") (pin "4") (pinfunction "V-_4") (pintype "power_in"))
      (node (ref "TP1") (pin "TP") (pinfunction "TP_TP") (pintype "input"))
    )
    (net (code "3") (name "-VCC-ISO-PRE") (class "Default")
      (node (ref "C12") (pin "1") (pinfunction "1_1") (pintype "passive"))
      (node (ref "F2") (pin "1") (pinfunction "1_1") (pintype "bidirectional"))
      (node (ref "U$1") (pin "1") (pinfunction "VOUT_1") (pintype "bidirectional"))
    )
    (net (code "4") (name "-VCC-PRE") (class "Default")
      (node (ref "C6") (pin "1") (pinfunction "1_1") (pintype "passive"))
      (node (ref "F3") (pin "1") (pinfunction "1_1") (pintype "bidirectional"))
      (node (ref "U$2") (pin "1") (pinfunction "VOUT_1") (pintype "bidirectional"))
    )
    (net (code "5") (name "3.3V-ISO") (class "Default")
      (node (ref "C29") (pin "1") (pinfunction "1_1") (pintype "passive"))
      (node (ref "Q2") (pin "1") (pinfunction "G_1") (pintype "passive"))
      (node (ref "Q3") (pin "1") (pinfunction "G_1") (pintype "passive"))
      (node (ref "R15") (pin "2") (pinfunction "2_2") (pintype "passive"))
      (node (ref "R19") (pin "2") (pinfunction "2_2") (pintype "passive"))
      (node (ref "U$15") (pin "5") (pinfunction "VOUT_5") (pintype "bidirectional"))
    )
    (net (code "6") (name "3V3OUT") (class "Default")
      (node (ref "C23") (pin "1") (pinfunction "1_1") (pintype "passive"))
      (node (ref "IC5") (pin "10") (pinfunction "3V3OUT_10") (pintype "output"))
      (node (ref "IC5") (pin "11") (pinfunction "~{RESET}_11") (pintype "input"))
      (node (ref "IC5") (pin "3") (pinfunction "VCCIO_3") (pintype "power_in"))
    )
    (net (code "7") (name "12V-ISO") (class "Default")
      (node (ref "C13") (pin "+") (pinfunction "+_+") (pintype "passive"))
      (node (ref "JP3") (pin "2") (pinfunction "2_2") (pintype "passive"))
      (node (ref "TP2") (pin "TP") (pinfunction "TP_TP") (pintype "input"))
      (node (ref "U1") (pin "3") (pinfunction "OUT_3") (pintype "output"))
    )
    (net (code "8") (name "CAMERA") (class "Default")
      (node (ref "IC1") (pin "3") (pinfunction "+IN_3") (pintype "input"))
      (node (ref "JP3") (pin "3") (pinfunction "3_3") (pintype "passive"))
      (node (ref "R6") (pin "1") (pinfunction "1_1") (pintype "passive"))
      (node (ref "R7") (pin "2") (pinfunction "2_2") (pintype "passive"))
    )
    (net (code "9") (name "GND") (class "Default")
      (node (ref "C14") (pin "2") (pinfunction "2_2") (pintype "passive"))
      (node (ref "C15") (pin "2") (pinfunction "2_2") (pintype "passive"))
      (node (ref "C16") (pin "C") (pinfunction "-_C") (pintype "passive"))
      (node (ref "C18") (pin "2") (pinfunction "2_2") (pintype "passive"))
      (node (ref "C19") (pin "2") (pinfunction "2_2") (pintype "passive"))
      (node (ref "C20") (pin "2") (pinfunction "2_2") (pintype "passive"))
      (node (ref "C21") (pin "2") (pinfunction "2_2") (pintype "passive"))
      (node (ref "C23") (pin "2") (pinfunction "2_2") (pintype "passive"))
      (node (ref "C27") (pin "2") (pinfunction "2_2") (pintype "passive"))
      (node (ref "C3") (pin "2") (pinfunction "2_2") (pintype "passive"))
      (node (ref "C4") (pin "2") (pinfunction "2_2") (pintype "passive"))
      (node (ref "C6") (pin "2") (pinfunction "2_2") (pintype "passive"))
      (node (ref "IC2") (pin "3") (pinfunction "+IN_3") (pintype "input"))
      (node (ref "IC3") (pin "4") (pinfunction "GND_4") (pintype "power_in"))
      (node (ref "IC5") (pin "13") (pinfunction "GND_13") (pintype "power_in"))
      (node (ref "IC5") (pin "5") (pinfunction "GND_5") (pintype "power_in"))
      (node (ref "JP15") (pin "4") (pinfunction "4_4") (pintype "passive"))
      (node (ref "JP6") (pin "SHELL") (pinfunction "SHELL_SHELL") (pintype "bidirectional"))
      (node (ref "JP7") (pin "8") (pinfunction "8_8") (pintype "passive"))
      (node (ref "R11") (pin "1") (pinfunction "1_1") (pintype "passive"))
      (node (ref "R39") (pin "1") (pinfunction "1_1") (pintype "passive"))
      (node (ref "U$12") (pin "1") (pinfunction "1_1") (pintype "passive"))
      (node (ref "U$2") (pin "2") (pinfunction "GND_2") (pintype "bidirectional"))
      (node (ref "U2") (pin "4") (pinfunction "GND_4") (pintype "input"))
      (node (ref "X2") (pin "GND") (pinfunction "GND_GND") (pintype "bidirectional"))
    )
    (net (code "10") (name "GND-ISO") (class "Default")
      (node (ref "C1") (pin "2") (pinfunction "2_2") (pintype "passive"))
      (node (ref "C10") (pin "C") (pinfunction "-_C") (pintype "passive"))
      (node (ref "C12") (pin "2") (pinfunction "2_2") (pintype "passive"))
      (node (ref "C13") (pin "-") (pinfunction "-_-") (pintype "passive"))
      (node (ref "C2") (pin "2") (pinfunction "2_2") (pintype "passive"))
      (node (ref "C22") (pin "2") (pinfunction "2_2") (pintype "passive"))
      (node (ref "C26") (pin "2") (pinfunction "2_2") (pintype "passive"))
      (node (ref "C28") (pin "2") (pinfunction "2_2") (pintype "passive"))
      (node (ref "C29") (pin "2") (pinfunction "2_2") (pintype "passive"))
      (node (ref "C7") (pin "2") (pinfunction "2_2") (pintype "passive"))
      (node (ref "C8") (pin "2") (pinfunction "2_2") (pintype "passive"))
      (node (ref "IC1") (pin "5") (pinfunction "+IN_5") (pintype "input"))
      (node (ref "IC4") (pin "4") (pinfunction "GND_4") (pintype "power_in"))
      (node (ref "JP1") (pin "4") (pinfunction "4_4") (pintype "passive"))
      (node (ref "JP2") (pin "8") (pinfunction "8_8") (pintype "passive"))
      (node (ref "JP3") (pin "1") (pinfunction "1_1") (pintype "passive"))
      (node (ref "JP5") (pin "1") (pinfunction "1_1") (pintype "passive"))
      (node (ref "Q1") (pin "2") (pinfunction "E_2") (pintype "passive"))
      (node (ref "R3") (pin "1") (pinfunction "1_1") (pintype "passive"))
      (node (ref "R35") (pin "1") (pinfunction "1_1") (pintype "passive"))
      (node (ref "R38") (pin "1") (pinfunction "1_1") (pintype "passive"))
      (node (ref "R7") (pin "1") (pinfunction "1_1") (pintype "passive"))
      (node (ref "U$1") (pin "2") (pinfunction "GND_2") (pintype "bidirectional"))
      (node (ref "U$10") (pin "1") (pinfunction "1_1") (pintype "passive"))
      (node (ref "U$11") (pin "6") (pinfunction "6_6") (pintype "bidirectional"))
      (node (ref "U$15") (pin "2") (pinfunction "GND_2") (pintype "bidirectional"))
      (node (ref "U$3") (pin "P$6") (pinfunction "6_P$6") (pintype "passive"))
      (node (ref "U1") (pin "4") (pinfunction "GND_4") (pintype "input"))
      (node (ref "U5") (pin "4") (pinfunction "GND_4") (pintype "input"))
    )
    (net (code "11") (name "Net-(C17-Pad2)") (class "Default")
      (node (ref "C17") (pin "2") (pinfunction "2_2") (pintype "passive"))
      (node (ref "R21") (pin "1") (pinfunction "1_1") (pintype "passive"))
    )
    (net (code "12") (name "Net-(C18-Pad1)") (class "Default")
      (node (ref "C18") (pin "1") (pinfunction "1_1") (pintype "passive"))
      (node (ref "R24") (pin "1") (pinfunction "1_1") (pintype "passive"))
      (node (ref "X2") (pin "D+") (pinfunction "D+_D+") (pintype "bidirectional"))
    )
    (net (code "13") (name "Net-(C19-Pad1)") (class "Default")
      (node (ref "C19") (pin "1") (pinfunction "1_1") (pintype "passive"))
      (node (ref "R23") (pin "1") (pinfunction "1_1") (pintype "passive"))
      (node (ref "X2") (pin "D-") (pinfunction "D-_D-") (pintype "bidirectional"))
    )
    (net (code "14") (name "Net-(F1-Pad1)") (class "Default")
      (node (ref "F1") (pin "1") (pinfunction "1_1") (pintype "bidirectional"))
      (node (ref "X2") (pin "VBUS") (pinfunction "VBUS_VBUS") (pintype "bidirectional"))
    )
    (net (code "15") (name "Net-(IC1A--IN)") (class "Default")
      (node (ref "IC1") (pin "2") (pinfunction "-IN_2") (pintype "input"))
      (node (ref "R2") (pin "1") (pinfunction "1_1") (pintype "passive"))
      (node (ref "R3") (pin "2") (pinfunction "2_2") (pintype "passive"))
    )
    (net (code "16") (name "Net-(IC1A-OUT)") (class "Default")
      (node (ref "IC1") (pin "1") (pinfunction "OUT_1") (pintype "output"))
      (node (ref "R1") (pin "1") (pinfunction "1_1") (pintype "passive"))
      (node (ref "R2") (pin "2") (pinfunction "2_2") (pintype "passive"))
    )
    (net (code "17") (name "Net-(IC1B--IN)") (class "Default")
      (node (ref "IC1") (pin "6") (pinfunction "-IN_6") (pintype "input"))
      (node (ref "R4") (pin "1") (pinfunction "1_1") (pintype "passive"))
      (node (ref "R6") (pin "2") (pinfunction "2_2") (pintype "passive"))
    )
    (net (code "18") (name "Net-(IC1B-OUT)") (class "Default")
      (node (ref "IC1") (pin "7") (pinfunction "OUT_7") (pintype "output"))
      (node (ref "R4") (pin "2") (pinfunction "2_2") (pintype "passive"))
      (node (ref "R5") (pin "1") (pinfunction "1_1") (pintype "passive"))
    )
    (net (code "19") (name "Net-(IC2A--IN)") (class "Default")
      (node (ref "IC2") (pin "2") (pinfunction "-IN_2") (pintype "input"))
      (node (ref "R13") (pin "1") (pinfunction "1_1") (pintype "passive"))
      (node (ref "R21") (pin "2") (pinfunction "2_2") (pintype "passive"))
      (node (ref "R22") (pin "2") (pinfunction "2_2") (pintype "passive"))
    )
    (net (code "20") (name "Net-(IC2A-OUT)") (class "Default")
      (node (ref "IC2") (pin "1") (pinfunction "OUT_1") (pintype "output"))
      (node (ref "R12") (pin "1") (pinfunction "1_1") (pintype "passive"))
      (node (ref "R18") (pin "2") (pinfunction "WIPER_2") (pintype "passive"))
      (node (ref "R18") (pin "3") (pinfunction "CW_3") (pintype "passive"))
    )
    (net (code "21") (name "Net-(IC2B-+IN)") (class "Default")
      (node (ref "IC2") (pin "5") (pinfunction "+IN_5") (pintype "input"))
      (node (ref "R10") (pin "2") (pinfunction "2_2") (pintype "passive"))
      (node (ref "R11") (pin "2") (pinfunction "2_2") (pintype "passive"))
    )
    (net (code "22") (name "Net-(IC2B--IN)") (class "Default")
      (node (ref "IC2") (pin "6") (pinfunction "-IN_6") (pintype "input"))
      (node (ref "R8") (pin "1") (pinfunction "1_1") (pintype "passive"))
      (node (ref "R9") (pin "2") (pinfunction "2_2") (pintype "passive"))
    )
    (net (code "23") (name "Net-(IC2B-OUT)") (class "Default")
      (node (ref "C17") (pin "1") (pinfunction "1_1") (pintype "passive"))
      (node (ref "IC2") (pin "7") (pinfunction "OUT_7") (pintype "output"))
      (node (ref "R22") (pin "1") (pinfunction "1_1") (pintype "passive"))
      (node (ref "R8") (pin "2") (pinfunction "2_2") (pintype "passive"))
    )
    (net (code "24") (name "Net-(IC5-USBDM)") (class "Default")
      (node (ref "IC5") (pin "9") (pinfunction "USBDM_9") (pintype "input"))
      (node (ref "R23") (pin "2") (pinfunction "2_2") (pintype "passive"))
    )
    (net (code "25") (name "Net-(IC5-USBDP)") (class "Default")
      (node (ref "IC5") (pin "8") (pinfunction "USBDP_8") (pintype "input"))
      (node (ref "R24") (pin "2") (pinfunction "2_2") (pintype "passive"))
    )
    (net (code "26") (name "Net-(LED1-PadC)") (class "Default")
      (node (ref "LED1") (pin "C") (pinfunction "C_C") (pintype "passive"))
      (node (ref "R38") (pin "2") (pinfunction "2_2") (pintype "passive"))
    )
    (net (code "27") (name "Net-(LED2-PadC)") (class "Default")
      (node (ref "LED2") (pin "C") (pinfunction "C_C") (pintype "passive"))
      (node (ref "R39") (pin "2") (pinfunction "2_2") (pintype "passive"))
    )
    (net (code "28") (name "Net-(Q1-B)") (class "Default")
      (node (ref "Q1") (pin "1") (pinfunction "B_1") (pintype "passive"))
      (node (ref "R32") (pin "2") (pinfunction "2_2") (pintype "passive"))
    )
    (net (code "29") (name "Net-(Q1-C)") (class "Default")
      (node (ref "Q1") (pin "3") (pinfunction "C_3") (pintype "passive"))
      (node (ref "R25") (pin "1") (pinfunction "1_1") (pintype "passive"))
    )
    (net (code "30") (name "Net-(R18-CCW)") (class "Default")
      (node (ref "R13") (pin "2") (pinfunction "2_2") (pintype "passive"))
      (node (ref "R18") (pin "1") (pinfunction "CCW_1") (pintype "passive"))
    )
    (net (code "31") (name "Net-(U$1-C1+)") (class "Default")
      (node (ref "C5") (pin "1") (pinfunction "1_1") (pintype "passive"))
      (node (ref "U$1") (pin "5") (pinfunction "C1+_5") (pintype "bidirectional"))
    )
    (net (code "32") (name "Net-(U$1-C1-)") (class "Default")
      (node (ref "C5") (pin "2") (pinfunction "2_2") (pintype "passive"))
      (node (ref "U$1") (pin "6") (pinfunction "C1-_6") (pintype "bidirectional"))
    )
    (net (code "33") (name "Net-(U$2-C1+)") (class "Default")
      (node (ref "C9") (pin "1") (pinfunction "1_1") (pintype "passive"))
      (node (ref "U$2") (pin "5") (pinfunction "C1+_5") (pintype "bidirectional"))
    )
    (net (code "34") (name "Net-(U$2-C1-)") (class "Default")
      (node (ref "C9") (pin "2") (pinfunction "2_2") (pintype "passive"))
      (node (ref "U$2") (pin "6") (pinfunction "C1-_6") (pintype "bidirectional"))
    )
    (net (code "35") (name "Net-(U$6-G)") (class "Default")
      (node (ref "D1") (pin "A") (pinfunction "A_A") (pintype "passive"))
      (node (ref "R25") (pin "2") (pinfunction "2_2") (pintype "passive"))
      (node (ref "R33") (pin "1") (pinfunction "1_1") (pintype "passive"))
      (node (ref "U$6") (pin "4") (pinfunction "G_4") (pintype "bidirectional"))
    )
    (net (code "36") (name "Net-(U$16-1)") (class "Default")
      (node (ref "C11") (pin "1") (pinfunction "1_1") (pintype "passive"))
      (node (ref "U$16") (pin "P$1") (pinfunction "1_P$1") (pintype "bidirectional"))
    )
    (net (code "37") (name "ROV-BATT") (class "Default")
      (node (ref "D1") (pin "C") (pinfunction "C_C") (pintype "passive"))
      (node (ref "R33") (pin "2") (pinfunction "2_2") (pintype "passive"))
      (node (ref "U$10") (pin "2") (pinfunction "2_2") (pintype "passive"))
      (node (ref "U$13") (pin "P$3") (pinfunction "3_P$3") (pintype "bidirectional"))
      (node (ref "U$6") (pin "1") (pinfunction "S_1") (pintype "bidirectional"))
      (node (ref "U$6") (pin "2") (pinfunction "S_2") (pintype "bidirectional"))
      (node (ref "U$6") (pin "3") (pinfunction "S_3") (pintype "bidirectional"))
    )
    (net (code "38") (name "ROV-ON") (class "Default")
      (node (ref "JP2") (pin "7") (pinfunction "7_7") (pintype "passive"))
      (node (ref "U$13") (pin "P$1") (pinfunction "1_P$1") (pintype "bidirectional"))
    )
    (net (code "39") (name "ROV-ON-CTRL") (class "Default")
      (node (ref "C11") (pin "2") (pinfunction "2_2") (pintype "passive"))
      (node (ref "JP7") (pin "7") (pinfunction "7_7") (pintype "passive"))
      (node (ref "R17") (pin "1") (pinfunction "1_1") (pintype "passive"))
    )
    (net (code "40") (name "ROV-ON-SELECT") (class "Default")
      (node (ref "R32") (pin "1") (pinfunction "1_1") (pintype "passive"))
      (node (ref "R35") (pin "2") (pinfunction "2_2") (pintype "passive"))
      (node (ref "U$13") (pin "P$2") (pinfunction "2_P$2") (pintype "bidirectional"))
    )
    (net (code "41") (name "ROV-RX") (class "Default")
      (node (ref "IC4") (pin "2") (pinfunction "RO_2") (pintype "output"))
      (node (ref "Q3") (pin "3") (pinfunction "D_3") (pintype "passive"))
      (node (ref "R20") (pin "1") (pinfunction "1_1") (pintype "passive"))
    )
    (net (code "42") (name "ROV-TP1+") (class "Default")
      (node (ref "JP2") (pin "1") (pinfunction "1_1") (pintype "passive"))
      (node (ref "R1") (pin "2") (pinfunction "2_2") (pintype "passive"))
    )
    (net (code "43") (name "ROV-TP1-") (class "Default")
      (node (ref "JP2") (pin "2") (pinfunction "2_2") (pintype "passive"))
      (node (ref "R5") (pin "2") (pinfunction "2_2") (pintype "passive"))
    )
    (net (code "44") (name "ROV-TP2+") (class "Default")
      (node (ref "IC4") (pin "5") (pinfunction "Y_5") (pintype "output"))
      (node (ref "JP2") (pin "3") (pinfunction "3_3") (pintype "passive"))
    )
    (net (code "45") (name "ROV-TP2-") (class "Default")
      (node (ref "IC4") (pin "6") (pinfunction "Z_6") (pintype "output"))
      (node (ref "JP2") (pin "4") (pinfunction "4_4") (pintype "passive"))
    )
    (net (code "46") (name "ROV-TP3+") (class "Default")
      (node (ref "IC4") (pin "8") (pinfunction "A_8") (pintype "input"))
      (node (ref "JP2") (pin "5") (pinfunction "5_5") (pintype "passive"))
    )
    (net (code "47") (name "ROV-TP3-") (class "Default")
      (node (ref "IC4") (pin "7") (pinfunction "B_7") (pintype "input"))
      (node (ref "JP2") (pin "6") (pinfunction "6_6") (pintype "passive"))
    )
    (net (code "48") (name "ROV-TX") (class "Default")
      (node (ref "IC4") (pin "3") (pinfunction "DI_3") (pintype "input"))
      (node (ref "Q2") (pin "3") (pinfunction "D_3") (pintype "passive"))
      (node (ref "R16") (pin "1") (pinfunction "1_1") (pintype "passive"))
    )
    (net (code "49") (name "ROV-VIN") (class "Default")
      (node (ref "C8") (pin "1") (pinfunction "1_1") (pintype "passive"))
      (node (ref "JP5") (pin "2") (pinfunction "2_2") (pintype "passive"))
      (node (ref "TP4") (pin "TP") (pinfunction "TP_TP") (pintype "input"))
      (node (ref "U$6") (pin "5") (pinfunction "D_5") (pintype "bidirectional"))
      (node (ref "U$6") (pin "6") (pinfunction "D_6") (pintype "bidirectional"))
      (node (ref "U$6") (pin "7") (pinfunction "D_7") (pintype "bidirectional"))
      (node (ref "U$6") (pin "8") (pinfunction "D_8") (pintype "bidirectional"))
      (node (ref "U1") (pin "1") (pinfunction "IN_1") (pintype "input"))
      (node (ref "U5") (pin "1") (pinfunction "IN_1") (pintype "input"))
    )
    (net (code "50") (name "RTS") (class "Default")
      (node (ref "IC5") (pin "2") (pinfunction "~{RTS}_2") (pintype "output"))
      (node (ref "U$16") (pin "P$2") (pinfunction "2_P$2") (pintype "bidirectional"))
    )
    (net (code "51") (name "RX-3.3V") (class "Default")
      (node (ref "JP1") (pin "2") (pinfunction "2_2") (pintype "passive"))
      (node (ref "Q3") (pin "2") (pinfunction "S_2") (pintype "passive"))
      (node (ref "R19") (pin "1") (pinfunction "1_1") (pintype "passive"))
      (node (ref "U$11") (pin "3") (pinfunction "3_3") (pintype "bidirectional"))
      (node (ref "U$3") (pin "P$3") (pinfunction "3_P$3") (pintype "passive"))
    )
    (net (code "52") (name "RX-I") (class "Default")
      (node (ref "IC3") (pin "2") (pinfunction "RO_2") (pintype "output"))
      (node (ref "IC5") (pin "4") (pinfunction "RXD_4") (pintype "input"))
      (node (ref "JP15") (pin "2") (pinfunction "2_2") (pintype "passive"))
    )
    (net (code "53") (name "TOP-TP1+") (class "Default")
      (node (ref "JP7") (pin "1") (pinfunction "1_1") (pintype "passive"))
      (node (ref "R14") (pin "2") (pinfunction "2_2") (pintype "passive"))
      (node (ref "R9") (pin "1") (pinfunction "1_1") (pintype "passive"))
    )
    (net (code "54") (name "TOP-TP1-") (class "Default")
      (node (ref "JP7") (pin "2") (pinfunction "2_2") (pintype "passive"))
      (node (ref "R10") (pin "1") (pinfunction "1_1") (pintype "passive"))
      (node (ref "R14") (pin "1") (pinfunction "1_1") (pintype "passive"))
    )
    (net (code "55") (name "TOP-TP2+") (class "Default")
      (node (ref "IC3") (pin "8") (pinfunction "A_8") (pintype "input"))
      (node (ref "JP7") (pin "3") (pinfunction "3_3") (pintype "passive"))
    )
    (net (code "56") (name "TOP-TP2-") (class "Default")
      (node (ref "IC3") (pin "7") (pinfunction "B_7") (pintype "input"))
      (node (ref "JP7") (pin "4") (pinfunction "4_4") (pintype "passive"))
    )
    (net (code "57") (name "TOP-TP3+") (class "Default")
      (node (ref "IC3") (pin "5") (pinfunction "Y_5") (pintype "output"))
      (node (ref "JP7") (pin "5") (pinfunction "5_5") (pintype "passive"))
    )
    (net (code "58") (name "TOP-TP3-") (class "Default")
      (node (ref "IC3") (pin "6") (pinfunction "Z_6") (pintype "output"))
      (node (ref "JP7") (pin "6") (pinfunction "6_6") (pintype "passive"))
    )
    (net (code "59") (name "TOP-VIN") (class "Default")
      (node (ref "C15") (pin "1") (pinfunction "1_1") (pintype "passive"))
      (node (ref "U$12") (pin "2") (pinfunction "2_2") (pintype "passive"))
      (node (ref "U2") (pin "1") (pinfunction "IN_1") (pintype "input"))
    )
    (net (code "60") (name "TX-3.3V") (class "Default")
      (node (ref "JP1") (pin "1") (pinfunction "1_1") (pintype "passive"))
      (node (ref "Q2") (pin "2") (pinfunction "S_2") (pintype "passive"))
      (node (ref "R15") (pin "1") (pinfunction "1_1") (pintype "passive"))
      (node (ref "U$11") (pin "2") (pinfunction "2_2") (pintype "bidirectional"))
      (node (ref "U$3") (pin "P$2") (pinfunction "2_P$2") (pintype "passive"))
    )
    (net (code "61") (name "TX-O") (class "Default")
      (node (ref "IC3") (pin "3") (pinfunction "DI_3") (pintype "input"))
      (node (ref "IC5") (pin "1") (pinfunction "TXD_1") (pintype "output"))
      (node (ref "JP15") (pin "1") (pinfunction "1_1") (pintype "passive"))
    )
    (net (code "62") (name "VCC") (class "Default")
      (node (ref "C14") (pin "1") (pinfunction "1_1") (pintype "passive"))
      (node (ref "C16") (pin "A") (pinfunction "+_A") (pintype "passive"))
      (node (ref "C20") (pin "1") (pinfunction "1_1") (pintype "passive"))
      (node (ref "C21") (pin "1") (pinfunction "1_1") (pintype "passive"))
      (node (ref "C27") (pin "1") (pinfunction "1_1") (pintype "passive"))
      (node (ref "C3") (pin "1") (pinfunction "1_1") (pintype "passive"))
      (node (ref "F1") (pin "2") (pinfunction "2_2") (pintype "bidirectional"))
      (node (ref "IC2") (pin "8") (pinfunction "V+_8") (pintype "power_in"))
      (node (ref "IC3") (pin "1") (pinfunction "VCC_1") (pintype "power_in"))
      (node (ref "IC5") (pin "12") (pinfunction "VCC_12") (pintype "power_in"))
      (node (ref "JP15") (pin "3") (pinfunction "3_3") (pintype "passive"))
      (node (ref "LED2") (pin "A") (pinfunction "A_A") (pintype "passive"))
      (node (ref "R17") (pin "2") (pinfunction "2_2") (pintype "passive"))
      (node (ref "TP5") (pin "TP") (pinfunction "TP_TP") (pintype "input"))
      (node (ref "U$2") (pin "3") (pinfunction "VIN_3") (pintype "bidirectional"))
      (node (ref "U$2") (pin "4") (pinfunction "EN_4") (pintype "bidirectional"))
      (node (ref "U2") (pin "3") (pinfunction "OUT_3") (pintype "output"))
    )
    (net (code "63") (name "VCC-ISO") (class "Default")
      (node (ref "C1") (pin "1") (pinfunction "1_1") (pintype "passive"))
      (node (ref "C10") (pin "A") (pinfunction "+_A") (pintype "passive"))
      (node (ref "C22") (pin "1") (pinfunction "1_1") (pintype "passive"))
      (node (ref "C26") (pin "1") (pinfunction "1_1") (pintype "passive"))
      (node (ref "C28") (pin "1") (pinfunction "1_1") (pintype "passive"))
      (node (ref "C7") (pin "1") (pinfunction "1_1") (pintype "passive"))
      (node (ref "IC1") (pin "8") (pinfunction "V+_8") (pintype "power_in"))
      (node (ref "IC4") (pin "1") (pinfunction "VCC_1") (pintype "power_in"))
      (node (ref "JP1") (pin "3") (pinfunction "3_3") (pintype "passive"))
      (node (ref "LED1") (pin "A") (pinfunction "A_A") (pintype "passive"))
      (node (ref "R16") (pin "2") (pinfunction "2_2") (pintype "passive"))
      (node (ref "R20") (pin "2") (pinfunction "2_2") (pintype "passive"))
      (node (ref "TP3") (pin "TP") (pinfunction "TP_TP") (pintype "input"))
      (node (ref "U$1") (pin "3") (pinfunction "VIN_3") (pintype "bidirectional"))
      (node (ref "U$1") (pin "4") (pinfunction "EN_4") (pintype "bidirectional"))
      (node (ref "U$11") (pin "1") (pinfunction "1_1") (pintype "bidirectional"))
      (node (ref "U$15") (pin "1") (pinfunction "VIN_1") (pintype "bidirectional"))
      (node (ref "U$15") (pin "3") (pinfunction "EN_3") (pintype "bidirectional"))
      (node (ref "U$3") (pin "P$1") (pinfunction "1_P$1") (pintype "passive"))
      (node (ref "U5") (pin "3") (pinfunction "OUT_3") (pintype "output"))
    )
    (net (code "64") (name "VIDEO-OUT") (class "Default")
      (node (ref "JP6") (pin "PIN") (pinfunction "PIN_PIN") (pintype "bidirectional"))
      (node (ref "R12") (pin "2") (pinfunction "2_2") (pintype "passive"))
    )
    (net (code "65") (name "unconnected-(IC5-CBUS0-Pad15)") (class "Default")
      (node (ref "IC5") (pin "15") (pinfunction "CBUS0_15") (pintype "bidirectional"))
    )
    (net (code "66") (name "unconnected-(IC5-CBUS1-Pad14)") (class "Default")
      (node (ref "IC5") (pin "14") (pinfunction "CBUS1_14") (pintype "bidirectional"))
    )
    (net (code "67") (name "unconnected-(IC5-CBUS2-Pad7)") (class "Default")
      (node (ref "IC5") (pin "7") (pinfunction "CBUS2_7") (pintype "bidirectional"))
    )
    (net (code "68") (name "unconnected-(IC5-CBUS3-Pad16)") (class "Default")
      (node (ref "IC5") (pin "16") (pinfunction "CBUS3_16") (pintype "bidirectional"))
    )
    (net (code "69") (name "unconnected-(IC5-~{CTS}-Pad6)") (class "Default")
      (node (ref "IC5") (pin "6") (pinfunction "~{CTS}_6") (pintype "input"))
    )
    (net (code "70") (name "unconnected-(JP6-PadSWITCH)") (class "Default")
      (node (ref "JP6") (pin "SWITCH") (pinfunction "SWITCH_SWITCH") (pintype "bidirectional"))
    )
    (net (code "71") (name "unconnected-(U$3-4-PadP$4)") (class "Default")
      (node (ref "U$3") (pin "P$4") (pinfunction "4_P$4") (pintype "passive"))
    )
    (net (code "72") (name "unconnected-(U$3-5-PadP$5)") (class "Default")
      (node (ref "U$3") (pin "P$5") (pinfunction "5_P$5") (pintype "passive"))
    )
    (net (code "73") (name "unconnected-(U$11-Pad4)") (class "Default")
      (node (ref "U$11") (pin "4") (pinfunction "4_4") (pintype "bidirectional"))
    )
    (net (code "74") (name "unconnected-(U$11-Pad5)") (class "Default")
      (node (ref "U$11") (pin "5") (pinfunction "5_5") (pintype "bidirectional"))
    )
  )
)
